# io-board-e-2.net
KiCad netlist of a schematic drawn in EAGLE
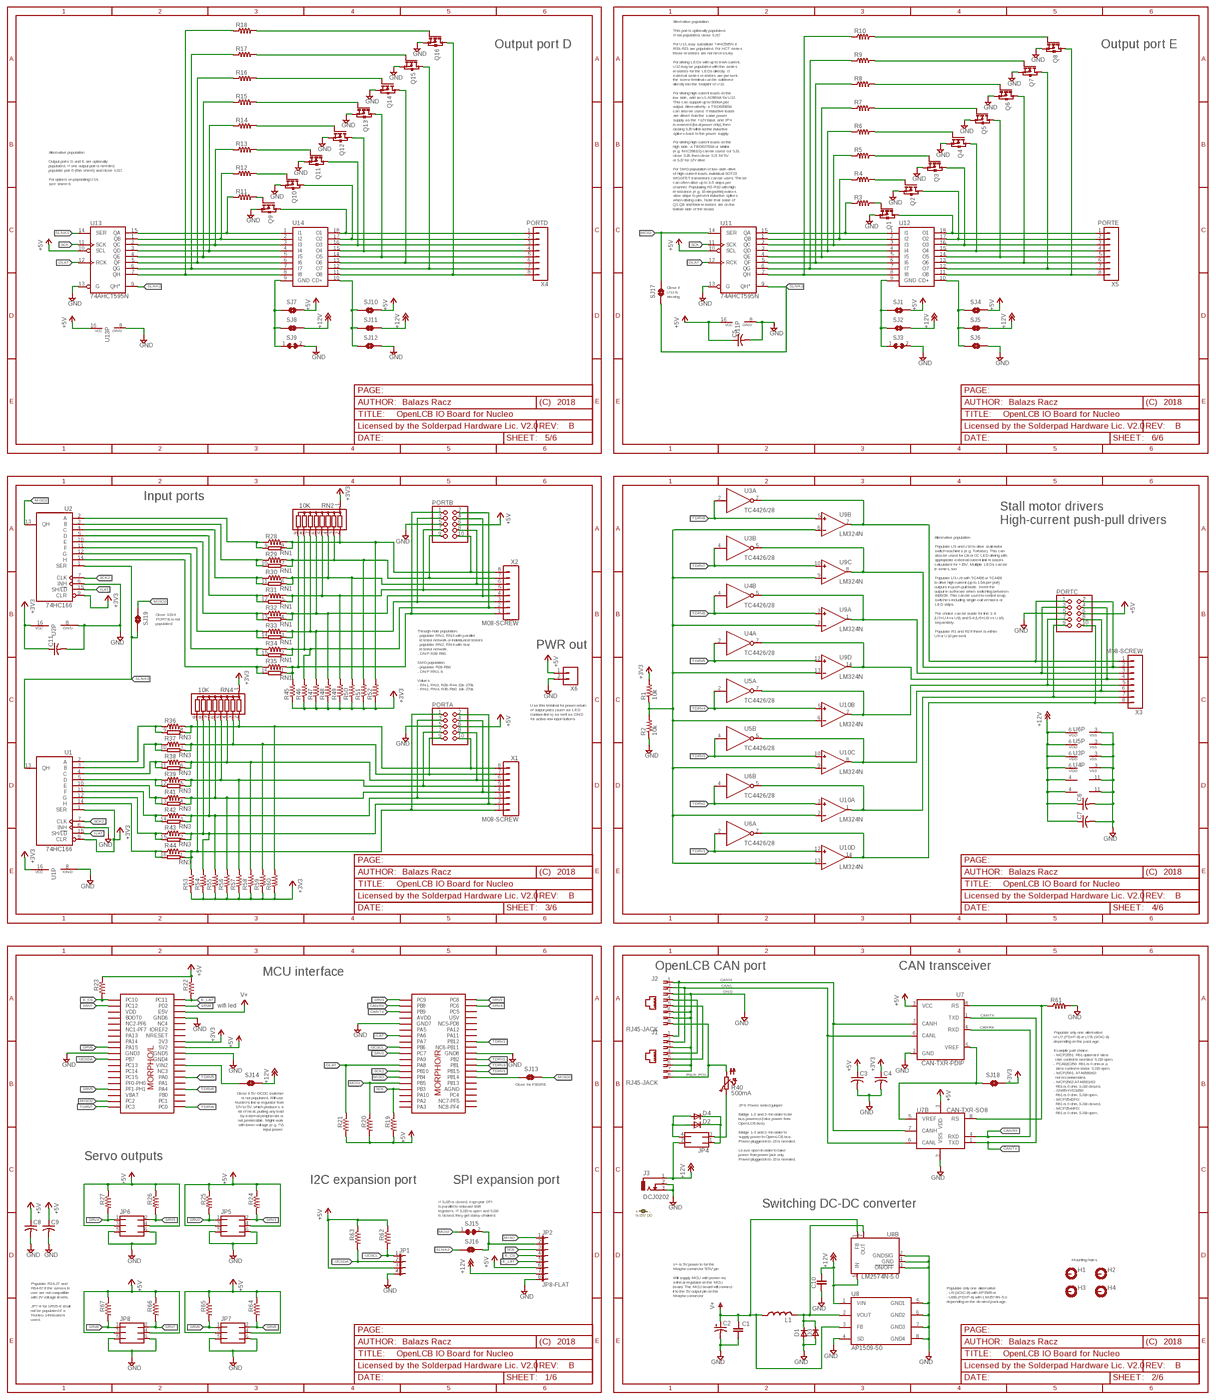
[diagram p0: schematic, sheet 1, overview]
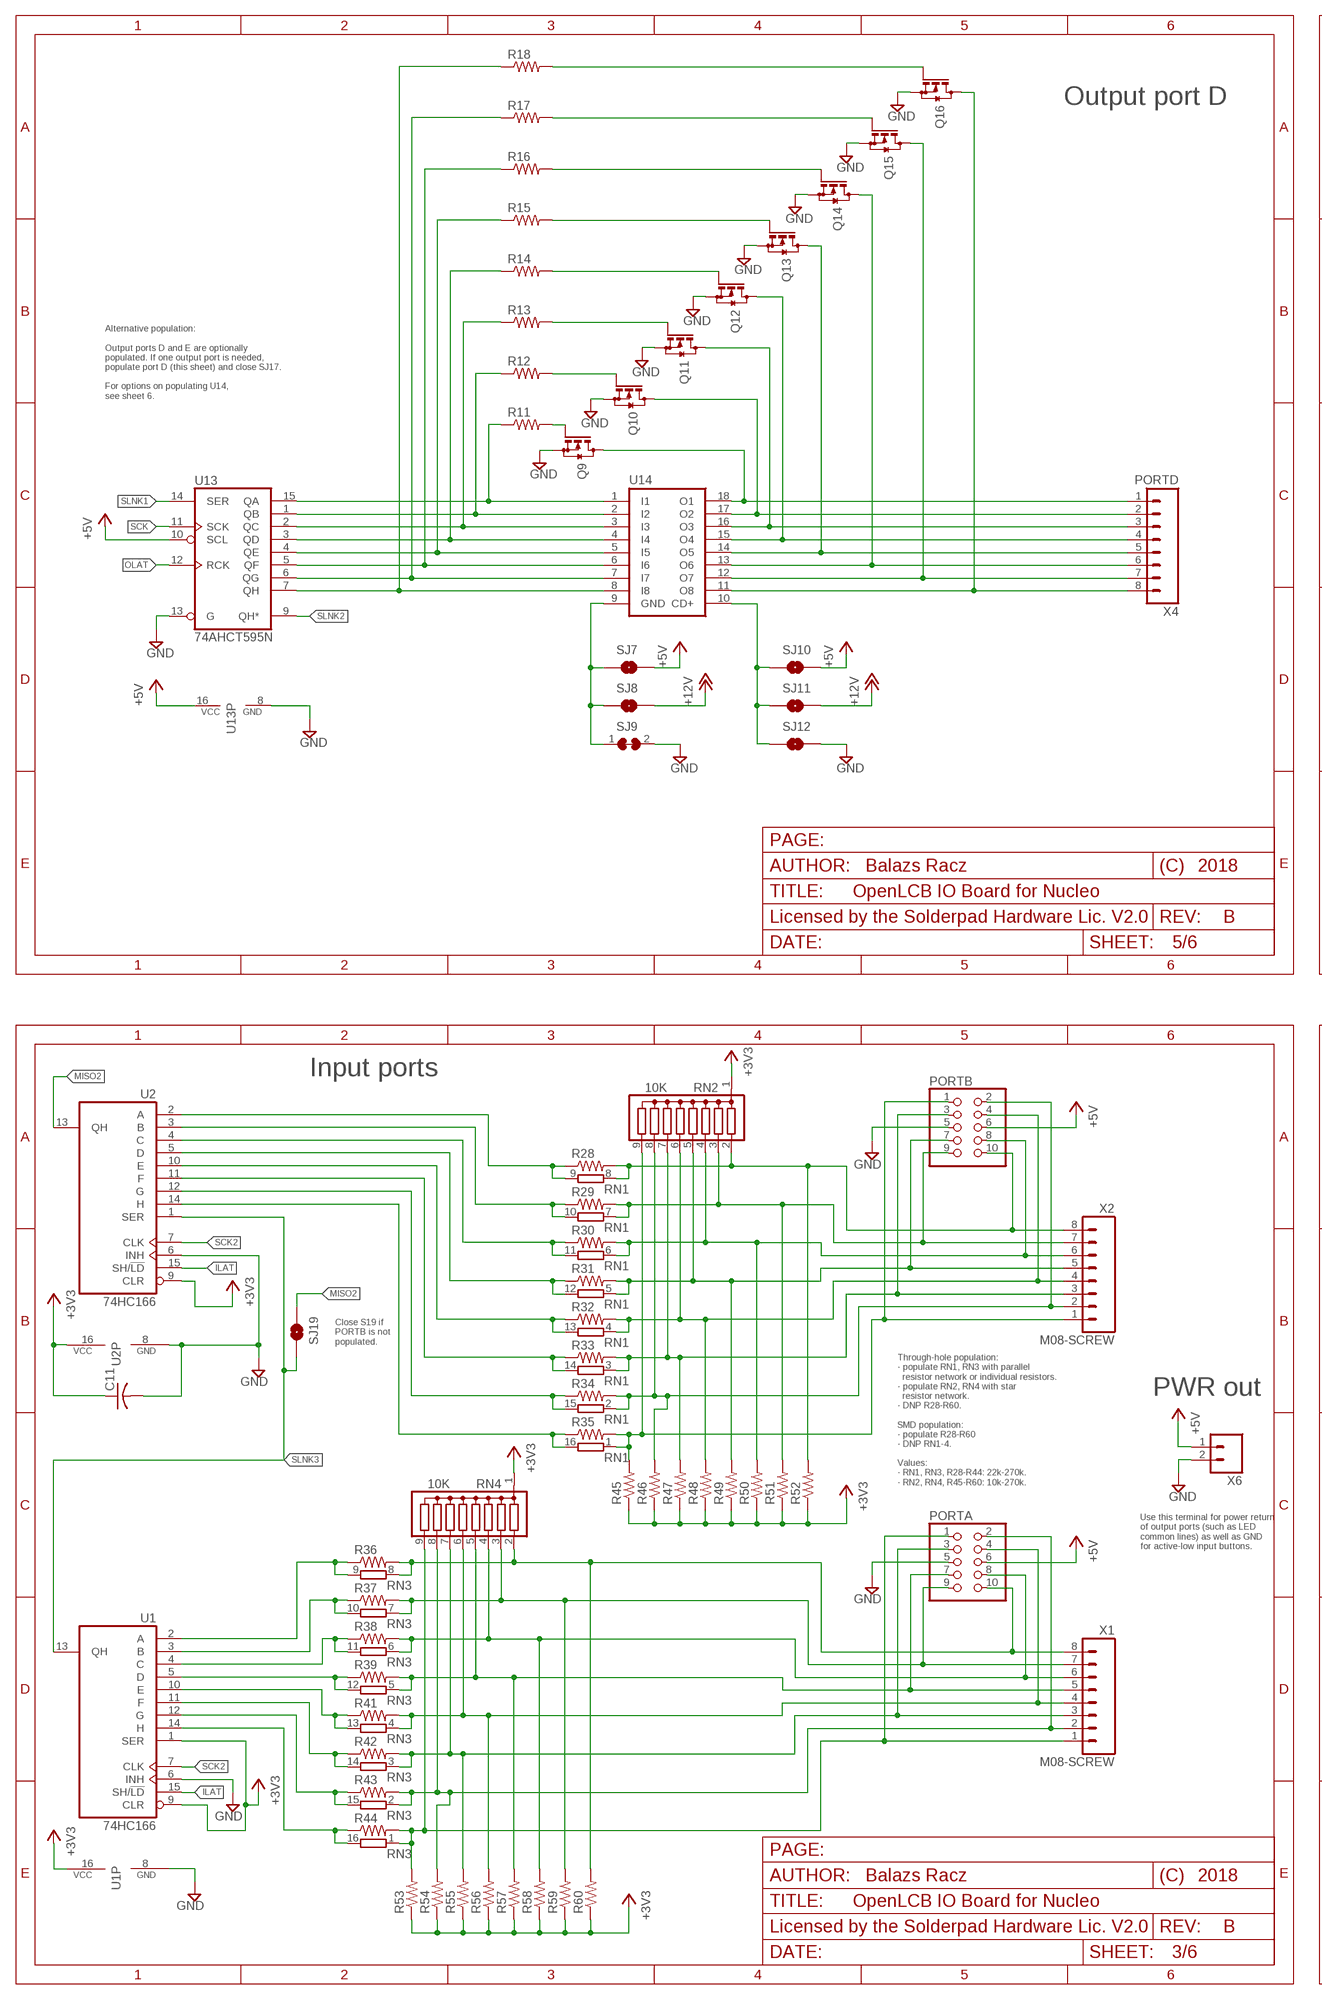
[diagram p1: schematic, sheet 1, part 1 of 4]
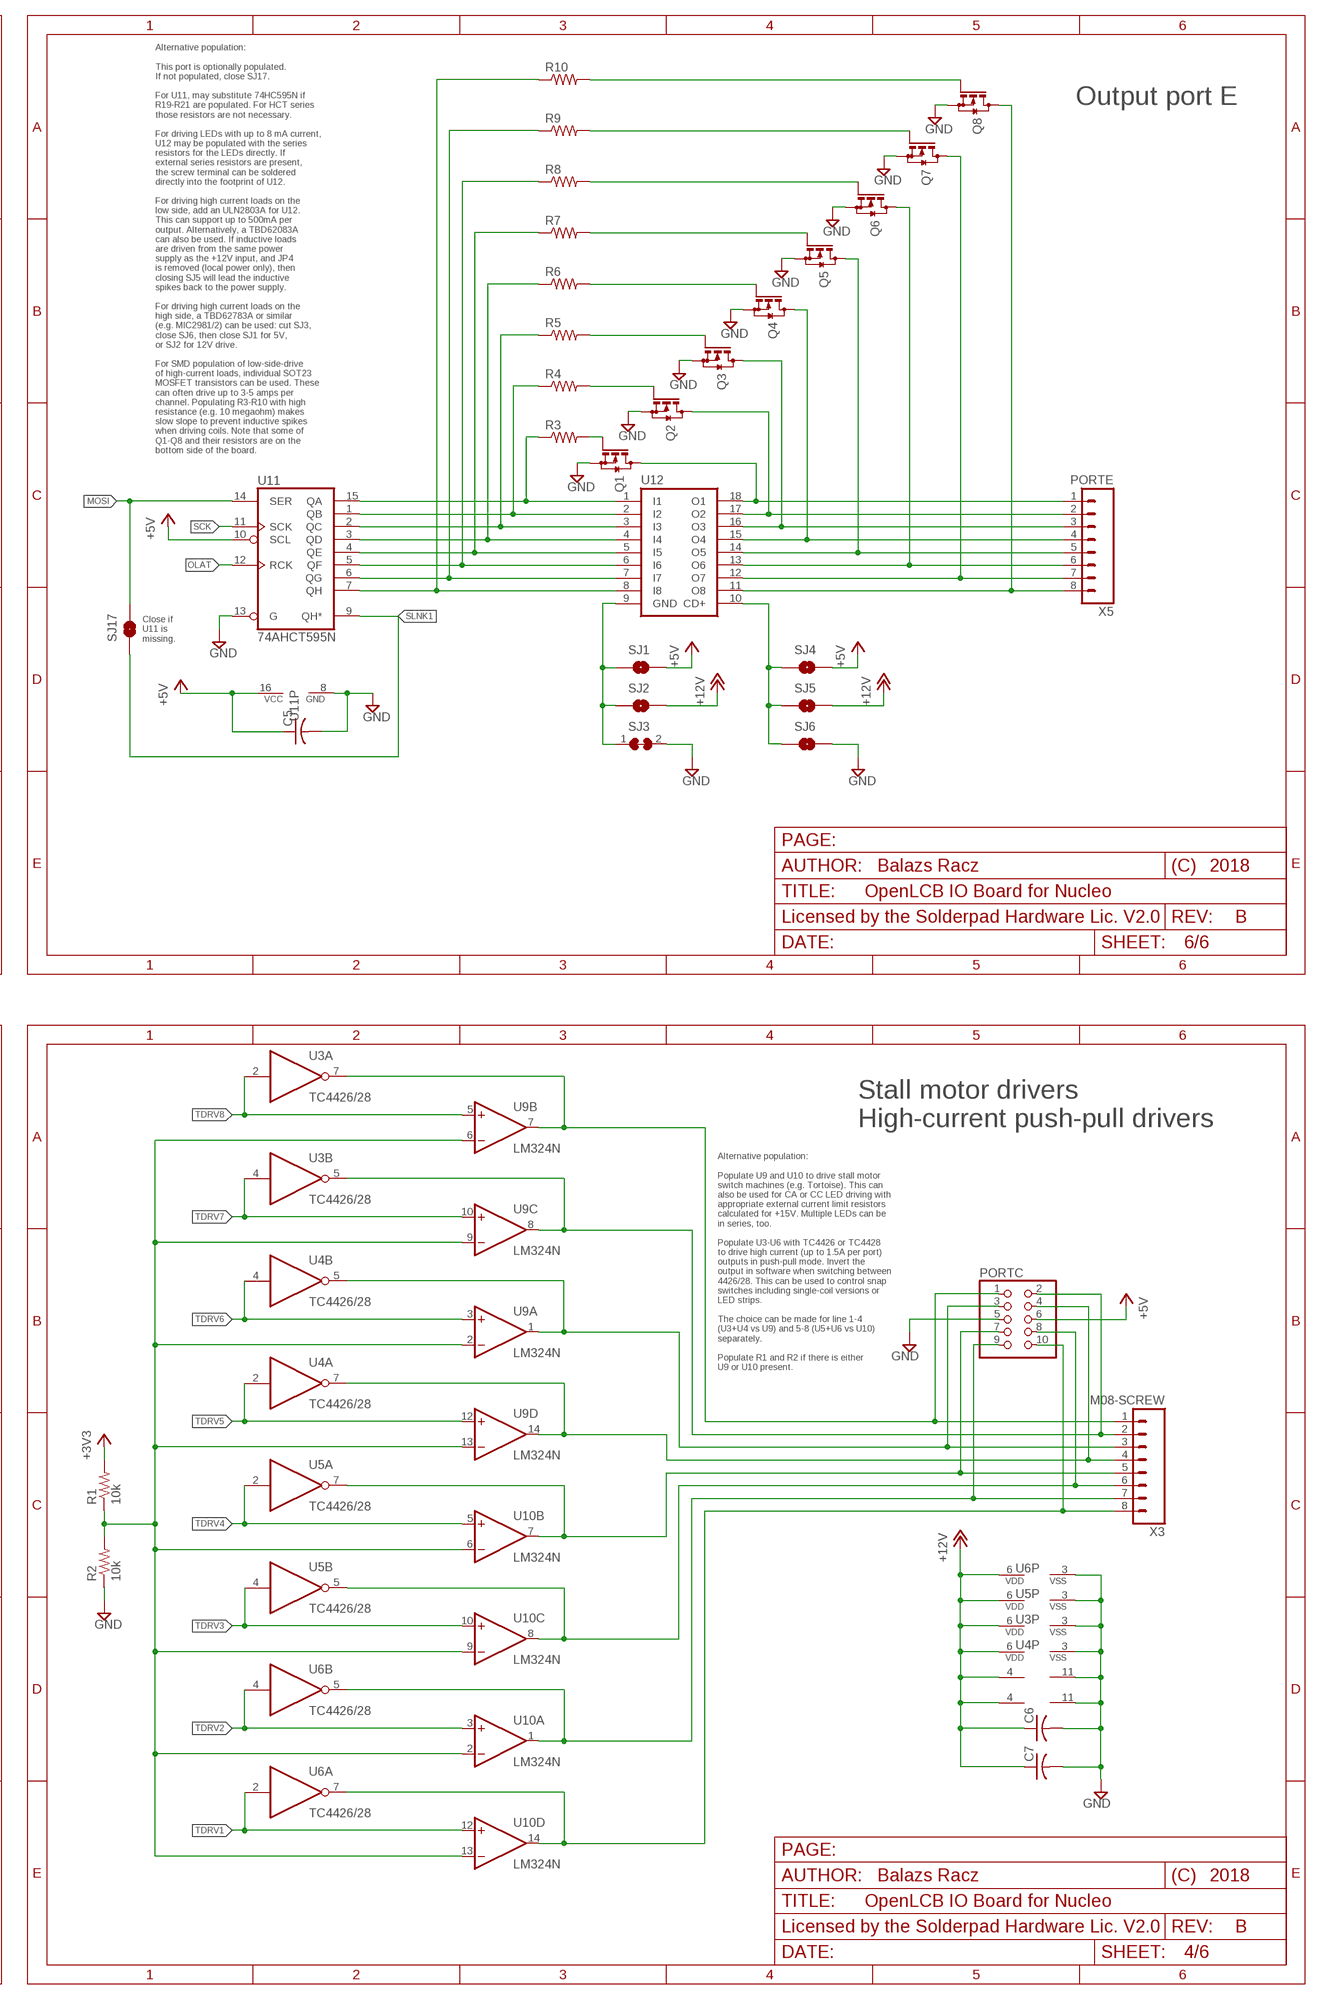
[diagram p2: schematic, sheet 1, part 2 of 4]
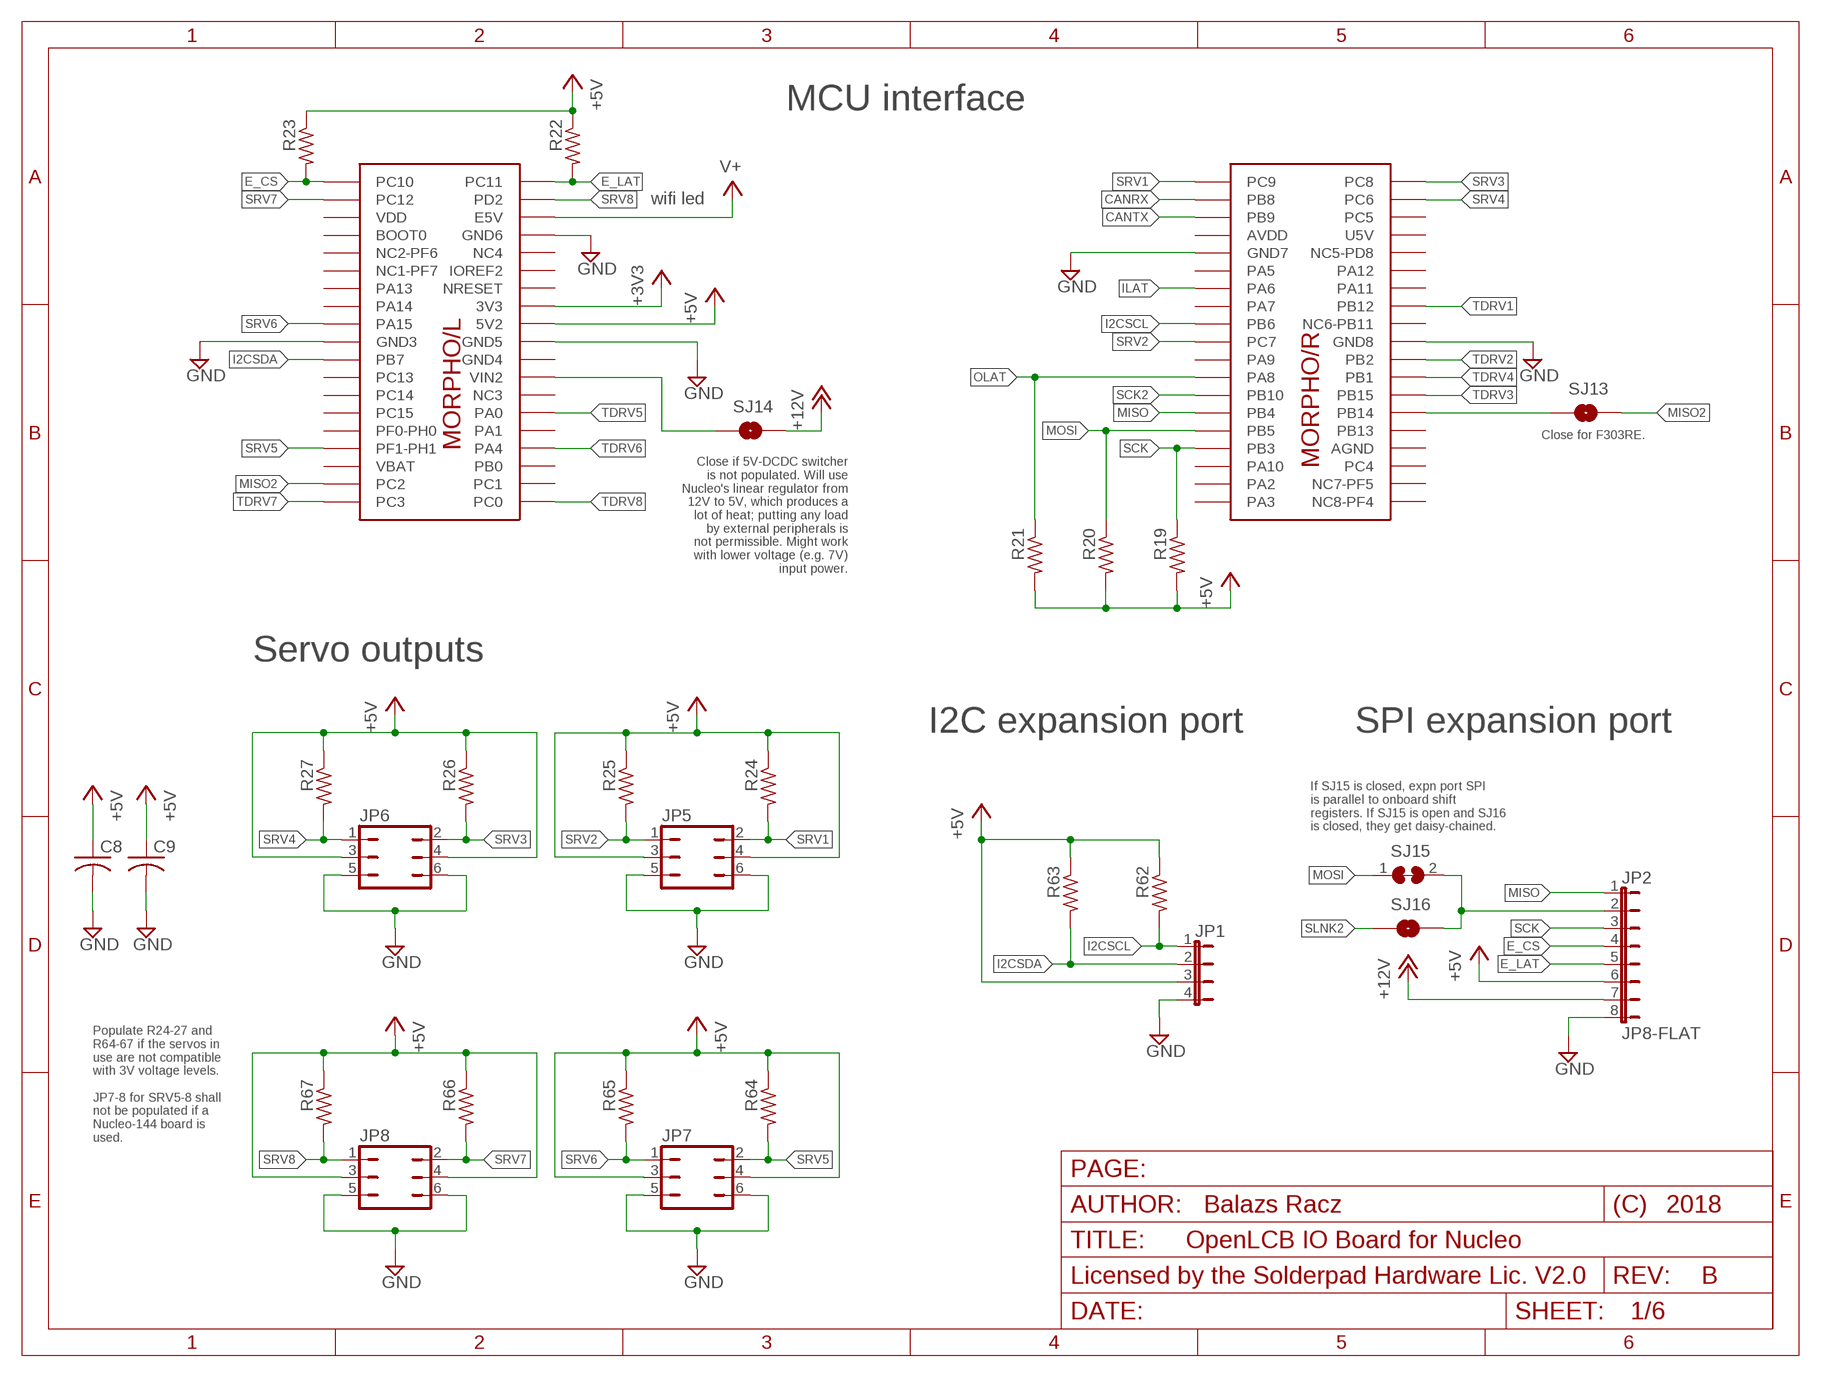
[diagram p3: schematic, sheet 1, part 3 of 4]
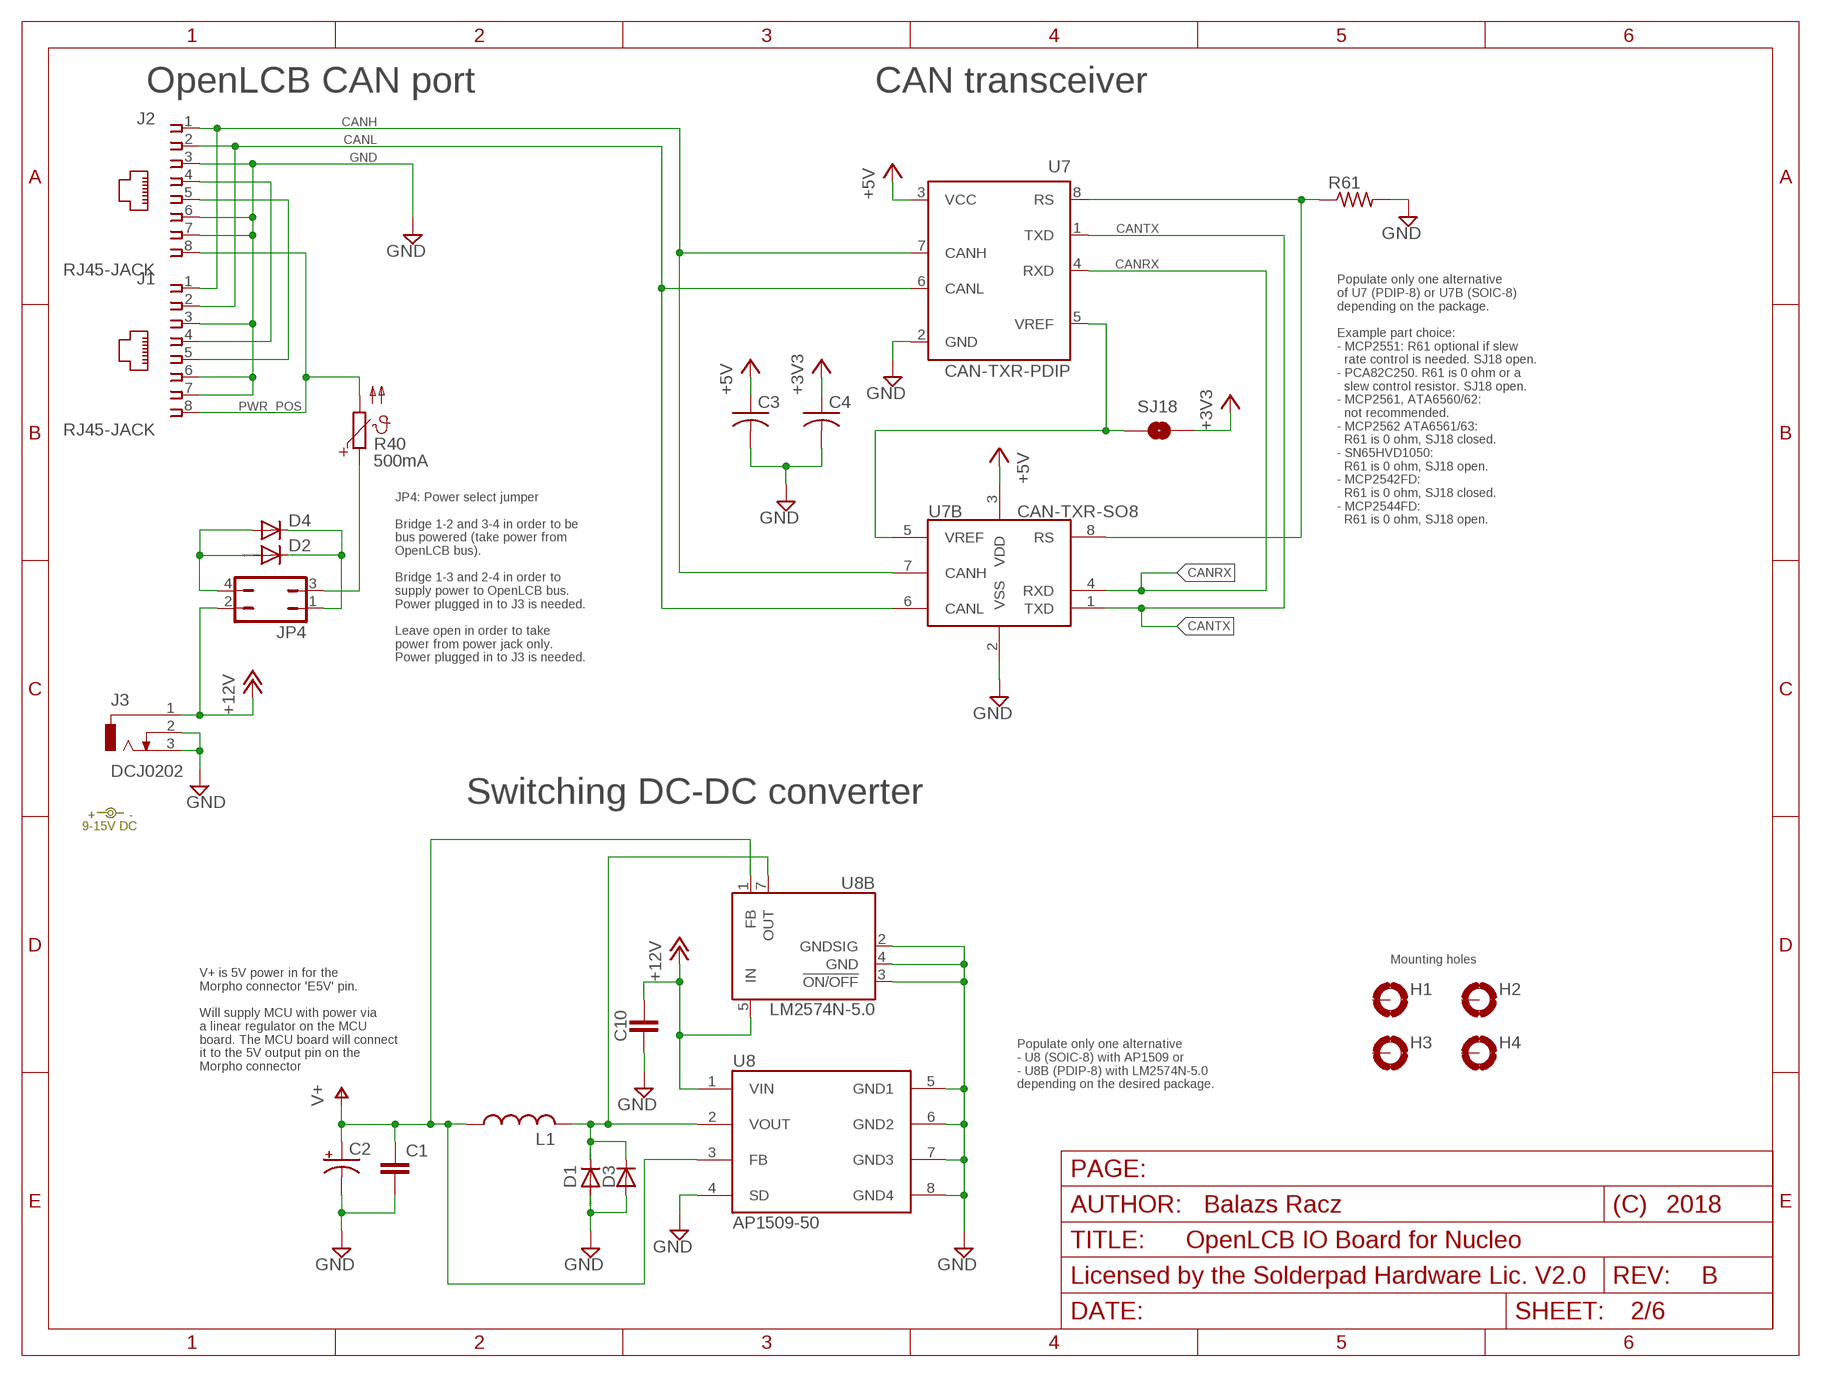
[diagram p4: schematic, sheet 1, part 4 of 4]

(export (version "E")
  (design (tool "Eeschema 10.0.6"))
  (components
    (comp (ref "+12V")
      (value "9-15V DC")
      (footprint "eagle-import:POWER_USAGE")
      (libsource (lib "eagle-import") (part "DOC-POWER_LABEL"))
    )
    (comp (ref "C1")
      (value "C-EUC1206")
      (footprint "eagle-import:C1206")
      (libsource (lib "eagle-import") (part "C-EUC1206"))
    )
    (comp (ref "C2")
      (value "CPOL-USE2.5-5")
      (footprint "eagle-import:E2,5-5")
      (libsource (lib "eagle-import") (part "CPOL-USE2.5-5"))
    )
    (comp (ref "C3")
      (value "C-USC0805")
      (footprint "eagle-import:C0805")
      (libsource (lib "eagle-import") (part "C-USC0805"))
    )
    (comp (ref "C4")
      (value "C-USC0805")
      (footprint "eagle-import:C0805")
      (libsource (lib "eagle-import") (part "C-USC0805"))
    )
    (comp (ref "C5")
      (value "C-USC0805")
      (footprint "eagle-import:C0805")
      (libsource (lib "eagle-import") (part "C-USC0805"))
    )
    (comp (ref "C6")
      (value "C-USC1206")
      (footprint "eagle-import:C1206")
      (libsource (lib "eagle-import") (part "C-USC1206"))
    )
    (comp (ref "C7")
      (value "C-USC1206")
      (footprint "eagle-import:C1206")
      (libsource (lib "eagle-import") (part "C-USC1206"))
    )
    (comp (ref "C8")
      (value "C-USC1206")
      (footprint "eagle-import:C1206")
      (libsource (lib "eagle-import") (part "C-USC1206"))
    )
    (comp (ref "C9")
      (value "C-USC1206")
      (footprint "eagle-import:C1206")
      (libsource (lib "eagle-import") (part "C-USC1206"))
    )
    (comp (ref "C10")
      (value "C-EUC1206")
      (footprint "eagle-import:C1206")
      (libsource (lib "eagle-import") (part "C-EUC1206"))
    )
    (comp (ref "C11")
      (value "C-USC0805")
      (footprint "eagle-import:C0805")
      (libsource (lib "eagle-import") (part "C-USC0805"))
    )
    (comp (ref "D1")
      (value "DIODE-DO41-7.6")
      (footprint "eagle-import:DO41-7.6")
      (libsource (lib "eagle-import") (part "DIODE-DO41-7.6"))
    )
    (comp (ref "D2")
      (value "DIODE-DO41-7.6")
      (footprint "eagle-import:DO41-7.6")
      (libsource (lib "eagle-import") (part "DIODE-DO41-7.6"))
    )
    (comp (ref "D3")
      (value "DIODEDO-214AA-NODOC")
      (footprint "eagle-import:DO214AA-NODOC")
      (libsource (lib "eagle-import") (part "DIODEDO-214AA-NODOC"))
    )
    (comp (ref "D4")
      (value "DIODEDO-214AA-NODOC")
      (footprint "eagle-import:DO214AA-NODOC")
      (libsource (lib "eagle-import") (part "DIODEDO-214AA-NODOC"))
    )
    (comp (ref "H1")
      (value "MOUNT-PAD-ROUND3.3")
      (footprint "eagle-import:3,3-PAD")
      (libsource (lib "eagle-import") (part "MOUNT-PAD-ROUND3.3"))
    )
    (comp (ref "H2")
      (value "MOUNT-PAD-ROUND3.3")
      (footprint "eagle-import:3,3-PAD")
      (libsource (lib "eagle-import") (part "MOUNT-PAD-ROUND3.3"))
    )
    (comp (ref "H3")
      (value "MOUNT-PAD-ROUND3.3")
      (footprint "eagle-import:3,3-PAD")
      (libsource (lib "eagle-import") (part "MOUNT-PAD-ROUND3.3"))
    )
    (comp (ref "H4")
      (value "MOUNT-PAD-ROUND3.3")
      (footprint "eagle-import:3,3-PAD")
      (libsource (lib "eagle-import") (part "MOUNT-PAD-ROUND3.3"))
    )
    (comp (ref "J1")
      (value "RJ45-JACK")
      (footprint "eagle-import:RJ45-PULSE-E5J88")
      (libsource (lib "eagle-import") (part "RJ45-JACKRJ45-PULSE-E5J00"))
    )
    (comp (ref "J2")
      (value "RJ45-JACK")
      (footprint "eagle-import:RJ45-PULSE-E5J88")
      (libsource (lib "eagle-import") (part "RJ45-JACKRJ45-PULSE-E5J00"))
    )
    (comp (ref "J3")
      (value "DCJ0202")
      (footprint "eagle-import:DCJ0202")
      (libsource (lib "eagle-import") (part "DCJ0202"))
    )
    (comp (ref "JP1")
      (value "JP4-FLAT")
      (footprint "eagle-import:JP4F")
      (libsource (lib "eagle-import") (part "JP4-FLAT"))
    )
    (comp (ref "JP2")
      (value "JP8-FLAT")
      (footprint "eagle-import:JP8F")
      (libsource (lib "eagle-import") (part "JP8-FLAT"))
    )
    (comp (ref "JP4")
      (value "JP2Q")
      (footprint "eagle-import:JP2Q")
      (libsource (lib "eagle-import") (part "JP2Q"))
    )
    (comp (ref "JP5")
      (value "JP3Q")
      (footprint "eagle-import:JP3Q")
      (libsource (lib "eagle-import") (part "JP3Q"))
    )
    (comp (ref "JP6")
      (value "JP3Q")
      (footprint "eagle-import:JP3Q")
      (libsource (lib "eagle-import") (part "JP3Q"))
    )
    (comp (ref "JP7")
      (value "JP3Q")
      (footprint "eagle-import:JP3Q")
      (libsource (lib "eagle-import") (part "JP3Q"))
    )
    (comp (ref "JP8")
      (value "JP3Q")
      (footprint "eagle-import:JP3Q")
      (libsource (lib "eagle-import") (part "JP3Q"))
    )
    (comp (ref "L1")
      (value "L-US")
      (footprint "eagle-import:L5-8,5")
      (libsource (lib "eagle-import") (part "L-US"))
    )
    (comp (ref "PORTA")
      (value "PINHD-2X5CN")
      (footprint "eagle-import:CON10M")
      (libsource (lib "eagle-import") (part "PINHD-2X5CN"))
    )
    (comp (ref "PORTB")
      (value "PINHD-2X5CN")
      (footprint "eagle-import:CON10M")
      (libsource (lib "eagle-import") (part "PINHD-2X5CN"))
    )
    (comp (ref "PORTC")
      (value "PINHD-2X5CN")
      (footprint "eagle-import:CON10M")
      (libsource (lib "eagle-import") (part "PINHD-2X5CN"))
    )
    (comp (ref "Q1")
      (value "BSS123")
      (footprint "eagle-import:SOT23")
      (libsource (lib "eagle-import") (part "BSS123"))
    )
    (comp (ref "Q2")
      (value "BSS123")
      (footprint "eagle-import:SOT23")
      (libsource (lib "eagle-import") (part "BSS123"))
    )
    (comp (ref "Q3")
      (value "BSS123")
      (footprint "eagle-import:SOT23")
      (libsource (lib "eagle-import") (part "BSS123"))
    )
    (comp (ref "Q4")
      (value "BSS123")
      (footprint "eagle-import:SOT23")
      (libsource (lib "eagle-import") (part "BSS123"))
    )
    (comp (ref "Q5")
      (value "BSS123")
      (footprint "eagle-import:SOT23")
      (libsource (lib "eagle-import") (part "BSS123"))
    )
    (comp (ref "Q6")
      (value "BSS123")
      (footprint "eagle-import:SOT23")
      (libsource (lib "eagle-import") (part "BSS123"))
    )
    (comp (ref "Q7")
      (value "BSS123")
      (footprint "eagle-import:SOT23")
      (libsource (lib "eagle-import") (part "BSS123"))
    )
    (comp (ref "Q8")
      (value "BSS123")
      (footprint "eagle-import:SOT23")
      (libsource (lib "eagle-import") (part "BSS123"))
    )
    (comp (ref "Q9")
      (value "BSS123")
      (footprint "eagle-import:SOT23")
      (libsource (lib "eagle-import") (part "BSS123"))
    )
    (comp (ref "Q10")
      (value "BSS123")
      (footprint "eagle-import:SOT23")
      (libsource (lib "eagle-import") (part "BSS123"))
    )
    (comp (ref "Q11")
      (value "BSS123")
      (footprint "eagle-import:SOT23")
      (libsource (lib "eagle-import") (part "BSS123"))
    )
    (comp (ref "Q12")
      (value "BSS123")
      (footprint "eagle-import:SOT23")
      (libsource (lib "eagle-import") (part "BSS123"))
    )
    (comp (ref "Q13")
      (value "BSS123")
      (footprint "eagle-import:SOT23")
      (libsource (lib "eagle-import") (part "BSS123"))
    )
    (comp (ref "Q14")
      (value "BSS123")
      (footprint "eagle-import:SOT23")
      (libsource (lib "eagle-import") (part "BSS123"))
    )
    (comp (ref "Q15")
      (value "BSS123")
      (footprint "eagle-import:SOT23")
      (libsource (lib "eagle-import") (part "BSS123"))
    )
    (comp (ref "Q16")
      (value "BSS123")
      (footprint "eagle-import:SOT23")
      (libsource (lib "eagle-import") (part "BSS123"))
    )
    (comp (ref "R1")
      (value "10k")
      (footprint "eagle-import:R0805")
      (libsource (lib "eagle-import") (part "R-US_R0805"))
    )
    (comp (ref "R2")
      (value "10k")
      (footprint "eagle-import:R0805")
      (libsource (lib "eagle-import") (part "R-US_R0805"))
    )
    (comp (ref "R3")
      (value "R-US_R0603")
      (footprint "eagle-import:R0603")
      (libsource (lib "eagle-import") (part "R-US_R0603"))
    )
    (comp (ref "R4")
      (value "R-US_R0603")
      (footprint "eagle-import:R0603")
      (libsource (lib "eagle-import") (part "R-US_R0603"))
    )
    (comp (ref "R5")
      (value "R-US_R0603")
      (footprint "eagle-import:R0603")
      (libsource (lib "eagle-import") (part "R-US_R0603"))
    )
    (comp (ref "R6")
      (value "R-US_R0603")
      (footprint "eagle-import:R0603")
      (libsource (lib "eagle-import") (part "R-US_R0603"))
    )
    (comp (ref "R7")
      (value "R-US_R0603")
      (footprint "eagle-import:R0603")
      (libsource (lib "eagle-import") (part "R-US_R0603"))
    )
    (comp (ref "R8")
      (value "R-US_R0603")
      (footprint "eagle-import:R0603")
      (libsource (lib "eagle-import") (part "R-US_R0603"))
    )
    (comp (ref "R9")
      (value "R-US_R0603")
      (footprint "eagle-import:R0603")
      (libsource (lib "eagle-import") (part "R-US_R0603"))
    )
    (comp (ref "R10")
      (value "R-US_R0603")
      (footprint "eagle-import:R0603")
      (libsource (lib "eagle-import") (part "R-US_R0603"))
    )
    (comp (ref "R11")
      (value "R-US_R0603")
      (footprint "eagle-import:R0603")
      (libsource (lib "eagle-import") (part "R-US_R0603"))
    )
    (comp (ref "R12")
      (value "R-US_R0603")
      (footprint "eagle-import:R0603")
      (libsource (lib "eagle-import") (part "R-US_R0603"))
    )
    (comp (ref "R13")
      (value "R-US_R0603")
      (footprint "eagle-import:R0603")
      (libsource (lib "eagle-import") (part "R-US_R0603"))
    )
    (comp (ref "R14")
      (value "R-US_R0603")
      (footprint "eagle-import:R0603")
      (libsource (lib "eagle-import") (part "R-US_R0603"))
    )
    (comp (ref "R15")
      (value "R-US_R0603")
      (footprint "eagle-import:R0603")
      (libsource (lib "eagle-import") (part "R-US_R0603"))
    )
    (comp (ref "R16")
      (value "R-US_R0603")
      (footprint "eagle-import:R0603")
      (libsource (lib "eagle-import") (part "R-US_R0603"))
    )
    (comp (ref "R17")
      (value "R-US_R0603")
      (footprint "eagle-import:R0603")
      (libsource (lib "eagle-import") (part "R-US_R0603"))
    )
    (comp (ref "R18")
      (value "R-US_R0603")
      (footprint "eagle-import:R0603")
      (libsource (lib "eagle-import") (part "R-US_R0603"))
    )
    (comp (ref "R19")
      (value "R-US_R0805")
      (footprint "eagle-import:R0805")
      (libsource (lib "eagle-import") (part "rcl_334_R-US_R0805"))
    )
    (comp (ref "R20")
      (value "R-US_R0805")
      (footprint "eagle-import:R0805")
      (libsource (lib "eagle-import") (part "rcl_334_R-US_R0805"))
    )
    (comp (ref "R21")
      (value "R-US_R0805")
      (footprint "eagle-import:R0805")
      (libsource (lib "eagle-import") (part "rcl_334_R-US_R0805"))
    )
    (comp (ref "R22")
      (value "R-US_R0805")
      (footprint "eagle-import:R0805")
      (libsource (lib "eagle-import") (part "rcl_334_R-US_R0805"))
    )
    (comp (ref "R23")
      (value "R-US_R0805")
      (footprint "eagle-import:R0805")
      (libsource (lib "eagle-import") (part "rcl_334_R-US_R0805"))
    )
    (comp (ref "R24")
      (value "R-US_R0805")
      (footprint "eagle-import:R0805")
      (libsource (lib "eagle-import") (part "rcl_334_R-US_R0805"))
    )
    (comp (ref "R25")
      (value "R-US_R0805")
      (footprint "eagle-import:R0805")
      (libsource (lib "eagle-import") (part "rcl_334_R-US_R0805"))
    )
    (comp (ref "R26")
      (value "R-US_R0805")
      (footprint "eagle-import:R0805")
      (libsource (lib "eagle-import") (part "rcl_334_R-US_R0805"))
    )
    (comp (ref "R27")
      (value "R-US_R0805")
      (footprint "eagle-import:R0805")
      (libsource (lib "eagle-import") (part "rcl_334_R-US_R0805"))
    )
    (comp (ref "R28")
      (value "R-US_R0603")
      (footprint "eagle-import:R0603")
      (libsource (lib "eagle-import") (part "rcl_334_R-US_R0603"))
    )
    (comp (ref "R29")
      (value "R-US_R0603")
      (footprint "eagle-import:R0603")
      (libsource (lib "eagle-import") (part "rcl_334_R-US_R0603"))
    )
    (comp (ref "R30")
      (value "R-US_R0603")
      (footprint "eagle-import:R0603")
      (libsource (lib "eagle-import") (part "rcl_334_R-US_R0603"))
    )
    (comp (ref "R31")
      (value "R-US_R0603")
      (footprint "eagle-import:R0603")
      (libsource (lib "eagle-import") (part "rcl_334_R-US_R0603"))
    )
    (comp (ref "R32")
      (value "R-US_R0603")
      (footprint "eagle-import:R0603")
      (libsource (lib "eagle-import") (part "rcl_334_R-US_R0603"))
    )
    (comp (ref "R33")
      (value "R-US_R0603")
      (footprint "eagle-import:R0603")
      (libsource (lib "eagle-import") (part "rcl_334_R-US_R0603"))
    )
    (comp (ref "R34")
      (value "R-US_R0603")
      (footprint "eagle-import:R0603")
      (libsource (lib "eagle-import") (part "rcl_334_R-US_R0603"))
    )
    (comp (ref "R35")
      (value "R-US_R0603")
      (footprint "eagle-import:R0603")
      (libsource (lib "eagle-import") (part "rcl_334_R-US_R0603"))
    )
    (comp (ref "R36")
      (value "R-US_R0603")
      (footprint "eagle-import:R0603")
      (libsource (lib "eagle-import") (part "rcl_334_R-US_R0603"))
    )
    (comp (ref "R37")
      (value "R-US_R0603")
      (footprint "eagle-import:R0603")
      (libsource (lib "eagle-import") (part "rcl_334_R-US_R0603"))
    )
    (comp (ref "R38")
      (value "R-US_R0603")
      (footprint "eagle-import:R0603")
      (libsource (lib "eagle-import") (part "rcl_334_R-US_R0603"))
    )
    (comp (ref "R39")
      (value "R-US_R0603")
      (footprint "eagle-import:R0603")
      (libsource (lib "eagle-import") (part "rcl_334_R-US_R0603"))
    )
    (comp (ref "R40")
      (value "500mA")
      (footprint "eagle-import:PTC1812")
      (libsource (lib "eagle-import") (part "PTC_1812"))
    )
    (comp (ref "R41")
      (value "R-US_R0603")
      (footprint "eagle-import:R0603")
      (libsource (lib "eagle-import") (part "rcl_334_R-US_R0603"))
    )
    (comp (ref "R42")
      (value "R-US_R0603")
      (footprint "eagle-import:R0603")
      (libsource (lib "eagle-import") (part "rcl_334_R-US_R0603"))
    )
    (comp (ref "R43")
      (value "R-US_R0603")
      (footprint "eagle-import:R0603")
      (libsource (lib "eagle-import") (part "rcl_334_R-US_R0603"))
    )
    (comp (ref "R44")
      (value "R-US_R0603")
      (footprint "eagle-import:R0603")
      (libsource (lib "eagle-import") (part "rcl_334_R-US_R0603"))
    )
    (comp (ref "R45")
      (value "R-US")
      (footprint "eagle-import:R0603")
      (libsource (lib "eagle-import") (part "R-US"))
    )
    (comp (ref "R46")
      (value "R-US")
      (footprint "eagle-import:R0603")
      (libsource (lib "eagle-import") (part "R-US"))
    )
    (comp (ref "R47")
      (value "R-US")
      (footprint "eagle-import:R0603")
      (libsource (lib "eagle-import") (part "R-US"))
    )
    (comp (ref "R48")
      (value "R-US")
      (footprint "eagle-import:R0603")
      (libsource (lib "eagle-import") (part "R-US"))
    )
    (comp (ref "R49")
      (value "R-US")
      (footprint "eagle-import:R0603")
      (libsource (lib "eagle-import") (part "R-US"))
    )
    (comp (ref "R50")
      (value "R-US")
      (footprint "eagle-import:R0603")
      (libsource (lib "eagle-import") (part "R-US"))
    )
    (comp (ref "R51")
      (value "R-US")
      (footprint "eagle-import:R0603")
      (libsource (lib "eagle-import") (part "R-US"))
    )
    (comp (ref "R52")
      (value "R-US")
      (footprint "eagle-import:R0603")
      (libsource (lib "eagle-import") (part "R-US"))
    )
    (comp (ref "R53")
      (value "R-US")
      (footprint "eagle-import:R0603")
      (libsource (lib "eagle-import") (part "R-US"))
    )
    (comp (ref "R54")
      (value "R-US")
      (footprint "eagle-import:R0603")
      (libsource (lib "eagle-import") (part "R-US"))
    )
    (comp (ref "R55")
      (value "R-US")
      (footprint "eagle-import:R0603")
      (libsource (lib "eagle-import") (part "R-US"))
    )
    (comp (ref "R56")
      (value "R-US")
      (footprint "eagle-import:R0603")
      (libsource (lib "eagle-import") (part "R-US"))
    )
    (comp (ref "R57")
      (value "R-US")
      (footprint "eagle-import:R0603")
      (libsource (lib "eagle-import") (part "R-US"))
    )
    (comp (ref "R58")
      (value "R-US")
      (footprint "eagle-import:R0603")
      (libsource (lib "eagle-import") (part "R-US"))
    )
    (comp (ref "R59")
      (value "R-US")
      (footprint "eagle-import:R0603")
      (libsource (lib "eagle-import") (part "R-US"))
    )
    (comp (ref "R60")
      (value "R-US")
      (footprint "eagle-import:R0603")
      (libsource (lib "eagle-import") (part "R-US"))
    )
    (comp (ref "R61")
      (value "R-US_R0805")
      (footprint "eagle-import:R0805")
      (libsource (lib "eagle-import") (part "rcl_334_R-US_R0805"))
    )
    (comp (ref "R62")
      (value "R-US_R0805")
      (footprint "eagle-import:R0805")
      (libsource (lib "eagle-import") (part "rcl_334_R-US_R0805"))
    )
    (comp (ref "R63")
      (value "R-US_R0805")
      (footprint "eagle-import:R0805")
      (libsource (lib "eagle-import") (part "rcl_334_R-US_R0805"))
    )
    (comp (ref "R64")
      (value "R-US_R0805")
      (footprint "eagle-import:R0805")
      (libsource (lib "eagle-import") (part "rcl_334_R-US_R0805"))
    )
    (comp (ref "R65")
      (value "R-US_R0805")
      (footprint "eagle-import:R0805")
      (libsource (lib "eagle-import") (part "rcl_334_R-US_R0805"))
    )
    (comp (ref "R66")
      (value "R-US_R0805")
      (footprint "eagle-import:R0805")
      (libsource (lib "eagle-import") (part "rcl_334_R-US_R0805"))
    )
    (comp (ref "R67")
      (value "R-US_R0805")
      (footprint "eagle-import:R0805")
      (libsource (lib "eagle-import") (part "rcl_334_R-US_R0805"))
    )
    (comp (ref "RN1")
      (value "8R-P")
      (footprint "eagle-import:DIL16")
      (libsource (lib "eagle-import") (part "8R-P"))
    )
    (comp (ref "RN2")
      (value "10K")
      (footprint "eagle-import:SIL9")
      (libsource (lib "eagle-import") (part "G08R"))
    )
    (comp (ref "RN3")
      (value "8R-P")
      (footprint "eagle-import:DIL16")
      (libsource (lib "eagle-import") (part "8R-P"))
    )
    (comp (ref "RN4")
      (value "10K")
      (footprint "eagle-import:SIL9")
      (libsource (lib "eagle-import") (part "G08R"))
    )
    (comp (ref "SJ1")
      (value "SJRND2")
      (footprint "eagle-import:SJ_RND2")
      (libsource (lib "eagle-import") (part "SJRND2"))
    )
    (comp (ref "SJ2")
      (value "SJRND2")
      (footprint "eagle-import:SJ_RND2")
      (libsource (lib "eagle-import") (part "SJRND2"))
    )
    (comp (ref "SJ3")
      (value "SJ-C")
      (footprint "eagle-import:SJW-C")
      (libsource (lib "eagle-import") (part "SJ-C"))
    )
    (comp (ref "SJ4")
      (value "SJRND2")
      (footprint "eagle-import:SJ_RND2")
      (libsource (lib "eagle-import") (part "SJRND2"))
    )
    (comp (ref "SJ5")
      (value "SJRND2")
      (footprint "eagle-import:SJ_RND2")
      (libsource (lib "eagle-import") (part "SJRND2"))
    )
    (comp (ref "SJ6")
      (value "SJRND2")
      (footprint "eagle-import:SJ_RND2")
      (libsource (lib "eagle-import") (part "SJRND2"))
    )
    (comp (ref "SJ7")
      (value "SJRND2")
      (footprint "eagle-import:SJ_RND2")
      (libsource (lib "eagle-import") (part "SJRND2"))
    )
    (comp (ref "SJ8")
      (value "SJRND2")
      (footprint "eagle-import:SJ_RND2")
      (libsource (lib "eagle-import") (part "SJRND2"))
    )
    (comp (ref "SJ9")
      (value "SJ-C")
      (footprint "eagle-import:SJW-C")
      (libsource (lib "eagle-import") (part "SJ-C"))
    )
    (comp (ref "SJ10")
      (value "SJRND2")
      (footprint "eagle-import:SJ_RND2")
      (libsource (lib "eagle-import") (part "SJRND2"))
    )
    (comp (ref "SJ11")
      (value "SJRND2")
      (footprint "eagle-import:SJ_RND2")
      (libsource (lib "eagle-import") (part "SJRND2"))
    )
    (comp (ref "SJ12")
      (value "SJRND2")
      (footprint "eagle-import:SJ_RND2")
      (libsource (lib "eagle-import") (part "SJRND2"))
    )
    (comp (ref "SJ13")
      (value "SJRND2")
      (footprint "eagle-import:SJ_RND2")
      (libsource (lib "eagle-import") (part "SJRND2"))
    )
    (comp (ref "SJ14")
      (value "SJRND2")
      (footprint "eagle-import:SJ_RND2")
      (libsource (lib "eagle-import") (part "SJRND2"))
    )
    (comp (ref "SJ15")
      (value "SJ-C")
      (footprint "eagle-import:SJW-C")
      (libsource (lib "eagle-import") (part "SJ-C"))
    )
    (comp (ref "SJ16")
      (value "SJRND2")
      (footprint "eagle-import:SJ_RND2")
      (libsource (lib "eagle-import") (part "SJRND2"))
    )
    (comp (ref "SJ17")
      (value "SJRND2")
      (footprint "eagle-import:SJ_RND2")
      (libsource (lib "eagle-import") (part "SJRND2"))
    )
    (comp (ref "SJ18")
      (value "SJRND2")
      (footprint "eagle-import:SJ_RND2")
      (libsource (lib "eagle-import") (part "SJRND2"))
    )
    (comp (ref "SJ19")
      (value "SJRND2")
      (footprint "eagle-import:SJ_RND2")
      (libsource (lib "eagle-import") (part "SJRND2"))
    )
    (comp (ref "U$1")
      (value "NUCLEO_64_GENERIC")
      (footprint "eagle-import:NUCLEO_BRD_BASE64")
      (libsource (lib "eagle-import") (part "NUCLEO_64_GENERIC"))
    )
    (comp (ref "U1")
      (value "74HC166")
      (footprint "eagle-import:DIL16")
      (libsource (lib "eagle-import") (part "74166N"))
    )
    (comp (ref "U2")
      (value "74HC166")
      (footprint "eagle-import:DIL16")
      (libsource (lib "eagle-import") (part "74166N"))
    )
    (comp (ref "U3")
      (value "TC4426/28")
      (footprint "eagle-import:DIL08-LONG")
      (libsource (lib "eagle-import") (part "TC4426APDIP"))
    )
    (comp (ref "U4")
      (value "TC4426/28")
      (footprint "eagle-import:DIL08-LONG")
      (libsource (lib "eagle-import") (part "TC4426APDIP"))
    )
    (comp (ref "U5")
      (value "TC4426/28")
      (footprint "eagle-import:DIL08-LONG")
      (libsource (lib "eagle-import") (part "TC4426APDIP"))
    )
    (comp (ref "U6")
      (value "TC4426/28")
      (footprint "eagle-import:DIL08-LONG")
      (libsource (lib "eagle-import") (part "TC4426APDIP"))
    )
    (comp (ref "U7")
      (value "CAN-TXR-PDIP")
      (footprint "eagle-import:DIL08")
      (libsource (lib "eagle-import") (part "PCA82C250"))
    )
    (comp (ref "U7B")
      (value "CAN-TXR-SO8")
      (footprint "eagle-import:SO-08")
      (libsource (lib "eagle-import") (part "MCP2551-SN"))
    )
    (comp (ref "U8")
      (value "AP1509-50")
      (footprint "eagle-import:SO-08")
      (libsource (lib "eagle-import") (part "AP1509"))
    )
    (comp (ref "U8B")
      (value "LM2574N-5.0")
      (footprint "eagle-import:DIL08")
      (libsource (lib "eagle-import") (part "LM2574?-N5.0"))
    )
    (comp (ref "U9")
      (value "LM324N")
      (footprint "eagle-import:DIL14")
      (libsource (lib "eagle-import") (part "LM324N"))
    )
    (comp (ref "U10")
      (value "LM324N")
      (footprint "eagle-import:DIL14")
      (libsource (lib "eagle-import") (part "LM324N"))
    )
    (comp (ref "U11")
      (value "74AHCT595N")
      (footprint "eagle-import:DIL16")
      (libsource (lib "eagle-import") (part "74595NHCT"))
    )
    (comp (ref "U12")
      (value "ULN2803A")
      (footprint "eagle-import:DIL18-THIN")
      (libsource (lib "eagle-import") (part "ULN2803A"))
    )
    (comp (ref "U13")
      (value "74AHCT595N")
      (footprint "eagle-import:DIL16")
      (libsource (lib "eagle-import") (part "74595NHCT"))
    )
    (comp (ref "U14")
      (value "ULN2803A")
      (footprint "eagle-import:DIL18-THIN")
      (libsource (lib "eagle-import") (part "ULN2803A"))
    )
    (comp (ref "X1")
      (value "M08-SCREW")
      (footprint "eagle-import:1X08_TERMINAL")
      (libsource (lib "eagle-import") (part "M08-SCREW"))
    )
    (comp (ref "X2")
      (value "M08-SCREW")
      (footprint "eagle-import:1X08_TERMINAL")
      (libsource (lib "eagle-import") (part "M08-SCREW"))
    )
    (comp (ref "X3")
      (value "M08-SCREW")
      (footprint "eagle-import:1X08_TERMINAL")
      (libsource (lib "eagle-import") (part "M08-SCREW"))
    )
    (comp (ref "X4")
      (value "PORTD")
      (footprint "eagle-import:1X08_TERMINAL")
      (libsource (lib "eagle-import") (part "M08-SCREW"))
    )
    (comp (ref "X5")
      (value "PORTE")
      (footprint "eagle-import:1X08_TERMINAL")
      (libsource (lib "eagle-import") (part "M08-SCREW"))
    )
    (comp (ref "X6")
      (value "CONNECTOR-M023.5MM-LOCK")
      (footprint "eagle-import:SCREWTERMINAL-3.5MM-2_LOCK")
      (libsource (lib "eagle-import") (part "CONNECTOR-M023.5MM-LOCK"))
    )
  )
  (nets
    (net (code "1") (name "+3V3") (class "Default")
      (node (ref "C11") (pin "1") (pinfunction "1_1") (pintype "passive"))
      (node (ref "C4") (pin "1") (pinfunction "1_1") (pintype "passive"))
      (node (ref "R1") (pin "2") (pinfunction "2_2") (pintype "passive"))
      (node (ref "R45") (pin "1") (pinfunction "1_1") (pintype "passive"))
      (node (ref "R46") (pin "1") (pinfunction "1_1") (pintype "passive"))
      (node (ref "R47") (pin "1") (pinfunction "1_1") (pintype "passive"))
      (node (ref "R48") (pin "1") (pinfunction "1_1") (pintype "passive"))
      (node (ref "R49") (pin "1") (pinfunction "1_1") (pintype "passive"))
      (node (ref "R50") (pin "1") (pinfunction "1_1") (pintype "passive"))
      (node (ref "R51") (pin "1") (pinfunction "1_1") (pintype "passive"))
      (node (ref "R52") (pin "1") (pinfunction "1_1") (pintype "passive"))
      (node (ref "R53") (pin "1") (pinfunction "1_1") (pintype "passive"))
      (node (ref "R54") (pin "1") (pinfunction "1_1") (pintype "passive"))
      (node (ref "R55") (pin "1") (pinfunction "1_1") (pintype "passive"))
      (node (ref "R56") (pin "1") (pinfunction "1_1") (pintype "passive"))
      (node (ref "R57") (pin "1") (pinfunction "1_1") (pintype "passive"))
      (node (ref "R58") (pin "1") (pinfunction "1_1") (pintype "passive"))
      (node (ref "R59") (pin "1") (pinfunction "1_1") (pintype "passive"))
      (node (ref "R60") (pin "1") (pinfunction "1_1") (pintype "passive"))
      (node (ref "RN2") (pin "1") (pinfunction "1_1") (pintype "passive"))
      (node (ref "RN4") (pin "1") (pinfunction "1_1") (pintype "passive"))
      (node (ref "SJ18") (pin "P$1") (pinfunction "1_P$1") (pintype "passive"))
      (node (ref "U$1") (pin "3V3") (pinfunction "3V3_3V3") (pintype "power_in"))
      (node (ref "U1") (pin "1") (pinfunction "SER_1") (pintype "input"))
      (node (ref "U1") (pin "16") (pinfunction "VCC_16") (pintype "power_in"))
      (node (ref "U1") (pin "9") (pinfunction "CLR_9") (pintype "input"))
      (node (ref "U2") (pin "16") (pinfunction "VCC_16") (pintype "power_in"))
      (node (ref "U2") (pin "9") (pinfunction "CLR_9") (pintype "input"))
    )
    (net (code "2") (name "+5V") (class "Default")
      (node (ref "C3") (pin "1") (pinfunction "1_1") (pintype "passive"))
      (node (ref "C5") (pin "1") (pinfunction "1_1") (pintype "passive"))
      (node (ref "C8") (pin "1") (pinfunction "1_1") (pintype "passive"))
      (node (ref "C9") (pin "1") (pinfunction "1_1") (pintype "passive"))
      (node (ref "JP1") (pin "3") (pinfunction "3_3") (pintype "passive"))
      (node (ref "JP2") (pin "6") (pinfunction "6_6") (pintype "passive"))
      (node (ref "JP5") (pin "3") (pinfunction "3_3") (pintype "passive"))
      (node (ref "JP5") (pin "4") (pinfunction "4_4") (pintype "passive"))
      (node (ref "JP6") (pin "3") (pinfunction "3_3") (pintype "passive"))
      (node (ref "JP6") (pin "4") (pinfunction "4_4") (pintype "passive"))
      (node (ref "JP7") (pin "3") (pinfunction "3_3") (pintype "passive"))
      (node (ref "JP7") (pin "4") (pinfunction "4_4") (pintype "passive"))
      (node (ref "JP8") (pin "3") (pinfunction "3_3") (pintype "passive"))
      (node (ref "JP8") (pin "4") (pinfunction "4_4") (pintype "passive"))
      (node (ref "PORTA") (pin "6") (pinfunction "6_6") (pintype "passive"))
      (node (ref "PORTB") (pin "6") (pinfunction "6_6") (pintype "passive"))
      (node (ref "PORTC") (pin "6") (pinfunction "6_6") (pintype "passive"))
      (node (ref "R19") (pin "2") (pinfunction "2_2") (pintype "passive"))
      (node (ref "R20") (pin "2") (pinfunction "2_2") (pintype "passive"))
      (node (ref "R21") (pin "2") (pinfunction "2_2") (pintype "passive"))
      (node (ref "R22") (pin "1") (pinfunction "1_1") (pintype "passive"))
      (node (ref "R23") (pin "1") (pinfunction "1_1") (pintype "passive"))
      (node (ref "R24") (pin "1") (pinfunction "1_1") (pintype "passive"))
      (node (ref "R25") (pin "1") (pinfunction "1_1") (pintype "passive"))
      (node (ref "R26") (pin "1") (pinfunction "1_1") (pintype "passive"))
      (node (ref "R27") (pin "1") (pinfunction "1_1") (pintype "passive"))
      (node (ref "R62") (pin "1") (pinfunction "1_1") (pintype "passive"))
      (node (ref "R63") (pin "1") (pinfunction "1_1") (pintype "passive"))
      (node (ref "R64") (pin "1") (pinfunction "1_1") (pintype "passive"))
      (node (ref "R65") (pin "1") (pinfunction "1_1") (pintype "passive"))
      (node (ref "R66") (pin "1") (pinfunction "1_1") (pintype "passive"))
      (node (ref "R67") (pin "1") (pinfunction "1_1") (pintype "passive"))
      (node (ref "SJ1") (pin "P$2") (pinfunction "2_P$2") (pintype "passive"))
      (node (ref "SJ10") (pin "P$2") (pinfunction "2_P$2") (pintype "passive"))
      (node (ref "SJ4") (pin "P$2") (pinfunction "2_P$2") (pintype "passive"))
      (node (ref "SJ7") (pin "P$2") (pinfunction "2_P$2") (pintype "passive"))
      (node (ref "U$1") (pin "5V2") (pinfunction "5V2_5V2") (pintype "power_in"))
      (node (ref "U11") (pin "10") (pinfunction "SCL_10") (pintype "input"))
      (node (ref "U11") (pin "16") (pinfunction "VCC_16") (pintype "power_in"))
      (node (ref "U13") (pin "10") (pinfunction "SCL_10") (pintype "input"))
      (node (ref "U13") (pin "16") (pinfunction "VCC_16") (pintype "power_in"))
      (node (ref "U7") (pin "3") (pinfunction "VCC_3") (pintype "power_in"))
      (node (ref "U7B") (pin "3") (pinfunction "VDD_3") (pintype "power_in"))
      (node (ref "X6") (pin "1") (pinfunction "1_1") (pintype "passive"))
    )
    (net (code "3") (name "+12V") (class "Default")
      (node (ref "C10") (pin "1") (pinfunction "1_1") (pintype "passive"))
      (node (ref "C6") (pin "1") (pinfunction "1_1") (pintype "passive"))
      (node (ref "C7") (pin "1") (pinfunction "1_1") (pintype "passive"))
      (node (ref "J3") (pin "1") (pinfunction "1_1") (pintype "passive"))
      (node (ref "JP2") (pin "7") (pinfunction "7_7") (pintype "passive"))
      (node (ref "JP4") (pin "2") (pinfunction "2_2") (pintype "passive"))
      (node (ref "SJ11") (pin "P$2") (pinfunction "2_P$2") (pintype "passive"))
      (node (ref "SJ14") (pin "P$2") (pinfunction "2_P$2") (pintype "passive"))
      (node (ref "SJ2") (pin "P$2") (pinfunction "2_P$2") (pintype "passive"))
      (node (ref "SJ5") (pin "P$2") (pinfunction "2_P$2") (pintype "passive"))
      (node (ref "SJ8") (pin "P$2") (pinfunction "2_P$2") (pintype "passive"))
      (node (ref "U10") (pin "4") (pinfunction "V+_4") (pintype "power_in"))
      (node (ref "U3") (pin "6") (pinfunction "VDD_6") (pintype "power_in"))
      (node (ref "U4") (pin "6") (pinfunction "VDD_6") (pintype "power_in"))
      (node (ref "U5") (pin "6") (pinfunction "VDD_6") (pintype "power_in"))
      (node (ref "U6") (pin "6") (pinfunction "VDD_6") (pintype "power_in"))
      (node (ref "U8") (pin "1") (pinfunction "VIN_1") (pintype "bidirectional"))
      (node (ref "U8B") (pin "5") (pinfunction "IN_5") (pintype "input"))
      (node (ref "U9") (pin "4") (pinfunction "V+_4") (pintype "power_in"))
    )
    (net (code "4") (name "/AGND") (class "Default")
      (node (ref "U$1") (pin "AGND") (pinfunction "AGND_AGND") (pintype "power_in"))
    )
    (net (code "5") (name "/AVDD") (class "Default")
      (node (ref "U$1") (pin "AVDD") (pinfunction "AVDD_AVDD") (pintype "power_in"))
    )
    (net (code "6") (name "/CANH") (class "Default")
      (node (ref "J1") (pin "1") (pinfunction "1_1") (pintype "passive"))
      (node (ref "J2") (pin "1") (pinfunction "1_1") (pintype "passive"))
      (node (ref "U7") (pin "7") (pinfunction "CANH_7") (pintype "bidirectional"))
      (node (ref "U7B") (pin "7") (pinfunction "CANH_7") (pintype "bidirectional"))
    )
    (net (code "7") (name "/CANL") (class "Default")
      (node (ref "J1") (pin "2") (pinfunction "2_2") (pintype "passive"))
      (node (ref "J2") (pin "2") (pinfunction "2_2") (pintype "passive"))
      (node (ref "U7") (pin "6") (pinfunction "CANL_6") (pintype "bidirectional"))
      (node (ref "U7B") (pin "6") (pinfunction "CANL_6") (pintype "bidirectional"))
    )
    (net (code "8") (name "/GND4") (class "Default")
      (node (ref "U$1") (pin "GND4") (pinfunction "GND4_GND4") (pintype "power_in"))
    )
    (net (code "9") (name "/PWR_POS") (class "Default")
      (node (ref "J1") (pin "8") (pinfunction "8_8") (pintype "passive"))
      (node (ref "J2") (pin "8") (pinfunction "8_8") (pintype "passive"))
      (node (ref "R40") (pin "2") (pinfunction "2_2") (pintype "passive"))
    )
    (net (code "10") (name "/U5V") (class "Default")
      (node (ref "U$1") (pin "U5V") (pinfunction "U5V_U5V") (pintype "power_in"))
    )
    (net (code "11") (name "/VBAT") (class "Default")
      (node (ref "U$1") (pin "VBAT") (pinfunction "VBAT_VBAT") (pintype "power_in"))
    )
    (net (code "12") (name "/VDD") (class "Default")
      (node (ref "U$1") (pin "VDD") (pinfunction "VDD_VDD") (pintype "power_in"))
    )
    (net (code "13") (name "CANRX") (class "Default")
      (node (ref "U$1") (pin "PB8") (pinfunction "PB8_PB8") (pintype "bidirectional"))
      (node (ref "U7") (pin "4") (pinfunction "RXD_4") (pintype "output"))
      (node (ref "U7B") (pin "4") (pinfunction "RXD_4") (pintype "bidirectional"))
    )
    (net (code "14") (name "CANTX") (class "Default")
      (node (ref "U$1") (pin "PB9") (pinfunction "PB9_PB9") (pintype "bidirectional"))
      (node (ref "U7") (pin "1") (pinfunction "TXD_1") (pintype "input"))
      (node (ref "U7B") (pin "1") (pinfunction "TXD_1") (pintype "bidirectional"))
    )
    (net (code "15") (name "E_CS") (class "Default")
      (node (ref "JP2") (pin "4") (pinfunction "4_4") (pintype "passive"))
      (node (ref "R23") (pin "2") (pinfunction "2_2") (pintype "passive"))
      (node (ref "U$1") (pin "PC10") (pinfunction "PC10_PC10") (pintype "bidirectional"))
    )
    (net (code "16") (name "E_LAT") (class "Default")
      (node (ref "JP2") (pin "5") (pinfunction "5_5") (pintype "passive"))
      (node (ref "R22") (pin "2") (pinfunction "2_2") (pintype "passive"))
      (node (ref "U$1") (pin "PC11") (pinfunction "PC11_PC11") (pintype "bidirectional"))
    )
    (net (code "17") (name "GND") (class "Default")
      (node (ref "C1") (pin "2") (pinfunction "2_2") (pintype "passive"))
      (node (ref "C10") (pin "2") (pinfunction "2_2") (pintype "passive"))
      (node (ref "C11") (pin "2") (pinfunction "2_2") (pintype "passive"))
      (node (ref "C2") (pin "-") (pinfunction "-_-") (pintype "passive"))
      (node (ref "C3") (pin "2") (pinfunction "2_2") (pintype "passive"))
      (node (ref "C4") (pin "2") (pinfunction "2_2") (pintype "passive"))
      (node (ref "C5") (pin "2") (pinfunction "2_2") (pintype "passive"))
      (node (ref "C6") (pin "2") (pinfunction "2_2") (pintype "passive"))
      (node (ref "C7") (pin "2") (pinfunction "2_2") (pintype "passive"))
      (node (ref "C8") (pin "2") (pinfunction "2_2") (pintype "passive"))
      (node (ref "C9") (pin "2") (pinfunction "2_2") (pintype "passive"))
      (node (ref "D1") (pin "A") (pinfunction "A_A") (pintype "passive"))
      (node (ref "D3") (pin "A") (pinfunction "A_A") (pintype "passive"))
      (node (ref "J1") (pin "3") (pinfunction "3_3") (pintype "passive"))
      (node (ref "J1") (pin "6") (pinfunction "6_6") (pintype "passive"))
      (node (ref "J1") (pin "7") (pinfunction "7_7") (pintype "passive"))
      (node (ref "J2") (pin "3") (pinfunction "3_3") (pintype "passive"))
      (node (ref "J2") (pin "6") (pinfunction "6_6") (pintype "passive"))
      (node (ref "J2") (pin "7") (pinfunction "7_7") (pintype "passive"))
      (node (ref "J3") (pin "2") (pinfunction "2_2") (pintype "passive"))
      (node (ref "J3") (pin "3") (pinfunction "3_3") (pintype "passive"))
      (node (ref "JP1") (pin "4") (pinfunction "4_4") (pintype "passive"))
      (node (ref "JP2") (pin "8") (pinfunction "8_8") (pintype "passive"))
      (node (ref "JP5") (pin "5") (pinfunction "5_5") (pintype "passive"))
      (node (ref "JP5") (pin "6") (pinfunction "6_6") (pintype "passive"))
      (node (ref "JP6") (pin "5") (pinfunction "5_5") (pintype "passive"))
      (node (ref "JP6") (pin "6") (pinfunction "6_6") (pintype "passive"))
      (node (ref "JP7") (pin "5") (pinfunction "5_5") (pintype "passive"))
      (node (ref "JP7") (pin "6") (pinfunction "6_6") (pintype "passive"))
      (node (ref "JP8") (pin "5") (pinfunction "5_5") (pintype "passive"))
      (node (ref "JP8") (pin "6") (pinfunction "6_6") (pintype "passive"))
      (node (ref "PORTA") (pin "5") (pinfunction "5_5") (pintype "passive"))
      (node (ref "PORTB") (pin "5") (pinfunction "5_5") (pintype "passive"))
      (node (ref "PORTC") (pin "5") (pinfunction "5_5") (pintype "passive"))
      (node (ref "Q1") (pin "2") (pinfunction "S_2") (pintype "passive"))
      (node (ref "Q10") (pin "2") (pinfunction "S_2") (pintype "passive"))
      (node (ref "Q11") (pin "2") (pinfunction "S_2") (pintype "passive"))
      (node (ref "Q12") (pin "2") (pinfunction "S_2") (pintype "passive"))
      (node (ref "Q13") (pin "2") (pinfunction "S_2") (pintype "passive"))
      (node (ref "Q14") (pin "2") (pinfunction "S_2") (pintype "passive"))
      (node (ref "Q15") (pin "2") (pinfunction "S_2") (pintype "passive"))
      (node (ref "Q16") (pin "2") (pinfunction "S_2") (pintype "passive"))
      (node (ref "Q2") (pin "2") (pinfunction "S_2") (pintype "passive"))
      (node (ref "Q3") (pin "2") (pinfunction "S_2") (pintype "passive"))
      (node (ref "Q4") (pin "2") (pinfunction "S_2") (pintype "passive"))
      (node (ref "Q5") (pin "2") (pinfunction "S_2") (pintype "passive"))
      (node (ref "Q6") (pin "2") (pinfunction "S_2") (pintype "passive"))
      (node (ref "Q7") (pin "2") (pinfunction "S_2") (pintype "passive"))
      (node (ref "Q8") (pin "2") (pinfunction "S_2") (pintype "passive"))
      (node (ref "Q9") (pin "2") (pinfunction "S_2") (pintype "passive"))
      (node (ref "R2") (pin "1") (pinfunction "1_1") (pintype "passive"))
      (node (ref "R61") (pin "2") (pinfunction "2_2") (pintype "passive"))
      (node (ref "SJ12") (pin "P$2") (pinfunction "2_P$2") (pintype "passive"))
      (node (ref "SJ3") (pin "2") (pinfunction "2_2") (pintype "passive"))
      (node (ref "SJ6") (pin "P$2") (pinfunction "2_P$2") (pintype "passive"))
      (node (ref "SJ9") (pin "2") (pinfunction "2_2") (pintype "passive"))
      (node (ref "U$1") (pin "GND3") (pinfunction "GND3_GND3") (pintype "power_in"))
      (node (ref "U$1") (pin "GND5") (pinfunction "GND5_GND5") (pintype "power_in"))
      (node (ref "U$1") (pin "GND6") (pinfunction "GND6_GND6") (pintype "power_in"))
      (node (ref "U$1") (pin "GND7") (pinfunction "GND7_GND7") (pintype "power_in"))
      (node (ref "U$1") (pin "GND8") (pinfunction "GND8_GND8") (pintype "power_in"))
      (node (ref "U1") (pin "6") (pinfunction "INH_6") (pintype "input"))
      (node (ref "U1") (pin "8") (pinfunction "GND_8") (pintype "power_in"))
      (node (ref "U10") (pin "11") (pinfunction "V-_11") (pintype "power_in"))
      (node (ref "U11") (pin "13") (pinfunction "G_13") (pintype "input"))
      (node (ref "U11") (pin "8") (pinfunction "GND_8") (pintype "power_in"))
      (node (ref "U13") (pin "13") (pinfunction "G_13") (pintype "input"))
      (node (ref "U13") (pin "8") (pinfunction "GND_8") (pintype "power_in"))
      (node (ref "U2") (pin "6") (pinfunction "INH_6") (pintype "input"))
      (node (ref "U2") (pin "8") (pinfunction "GND_8") (pintype "power_in"))
      (node (ref "U3") (pin "3") (pinfunction "VSS_3") (pintype "power_in"))
      (node (ref "U4") (pin "3") (pinfunction "VSS_3") (pintype "power_in"))
      (node (ref "U5") (pin "3") (pinfunction "VSS_3") (pintype "power_in"))
      (node (ref "U6") (pin "3") (pinfunction "VSS_3") (pintype "power_in"))
      (node (ref "U7") (pin "2") (pinfunction "GND_2") (pintype "power_in"))
      (node (ref "U7B") (pin "2") (pinfunction "VSS_2") (pintype "power_in"))
      (node (ref "U8") (pin "4") (pinfunction "SD_4") (pintype "bidirectional"))
      (node (ref "U8") (pin "5") (pinfunction "GND1_5") (pintype "power_in"))
      (node (ref "U8") (pin "6") (pinfunction "GND2_6") (pintype "power_in"))
      (node (ref "U8") (pin "7") (pinfunction "GND3_7") (pintype "power_in"))
      (node (ref "U8") (pin "8") (pinfunction "GND4_8") (pintype "power_in"))
      (node (ref "U8B") (pin "2") (pinfunction "GNDSIG_2") (pintype "input"))
      (node (ref "U8B") (pin "3") (pinfunction "~{ON/OFF}_3") (pintype "input"))
      (node (ref "U8B") (pin "4") (pinfunction "GND_4") (pintype "power_in"))
      (node (ref "U9") (pin "11") (pinfunction "V-_11") (pintype "power_in"))
      (node (ref "X6") (pin "2") (pinfunction "2_2") (pintype "passive"))
    )
    (net (code "18") (name "I2CSCL") (class "Default")
      (node (ref "JP1") (pin "1") (pinfunction "1_1") (pintype "passive"))
      (node (ref "R62") (pin "2") (pinfunction "2_2") (pintype "passive"))
      (node (ref "U$1") (pin "PB6") (pinfunction "PB6_PB6") (pintype "bidirectional"))
    )
    (net (code "19") (name "I2CSDA") (class "Default")
      (node (ref "JP1") (pin "2") (pinfunction "2_2") (pintype "passive"))
      (node (ref "R63") (pin "2") (pinfunction "2_2") (pintype "passive"))
      (node (ref "U$1") (pin "PB7") (pinfunction "PB7_PB7") (pintype "bidirectional"))
    )
    (net (code "20") (name "ILAT") (class "Default")
      (node (ref "U$1") (pin "PA6") (pinfunction "PA6_PA6") (pintype "bidirectional"))
      (node (ref "U1") (pin "15") (pinfunction "SH/~{LD}_15") (pintype "input"))
      (node (ref "U2") (pin "15") (pinfunction "SH/~{LD}_15") (pintype "input"))
    )
    (net (code "21") (name "MISO") (class "Default")
      (node (ref "JP2") (pin "1") (pinfunction "1_1") (pintype "passive"))
      (node (ref "U$1") (pin "PB4") (pinfunction "PB4_PB4") (pintype "bidirectional"))
    )
    (net (code "22") (name "MISO2") (class "Default")
      (node (ref "SJ13") (pin "P$2") (pinfunction "2_P$2") (pintype "passive"))
      (node (ref "SJ19") (pin "P$2") (pinfunction "2_P$2") (pintype "passive"))
      (node (ref "U$1") (pin "PC2") (pinfunction "PC2_PC2") (pintype "bidirectional"))
      (node (ref "U2") (pin "13") (pinfunction "QH_13") (pintype "output"))
    )
    (net (code "23") (name "MOSI") (class "Default")
      (node (ref "R20") (pin "1") (pinfunction "1_1") (pintype "passive"))
      (node (ref "SJ15") (pin "1") (pinfunction "1_1") (pintype "passive"))
      (node (ref "SJ17") (pin "P$2") (pinfunction "2_P$2") (pintype "passive"))
      (node (ref "U$1") (pin "PB5") (pinfunction "PB5_PB5") (pintype "bidirectional"))
      (node (ref "U11") (pin "14") (pinfunction "SER_14") (pintype "input"))
    )
    (net (code "24") (name "Net-(D2-PadA)") (class "Default")
      (node (ref "D2") (pin "A") (pinfunction "A_A") (pintype "passive"))
      (node (ref "D4") (pin "A") (pinfunction "A_A") (pintype "passive"))
      (node (ref "JP4") (pin "4") (pinfunction "4_4") (pintype "passive"))
    )
    (net (code "25") (name "Net-(D2-PadC)") (class "Default")
      (node (ref "D2") (pin "C") (pinfunction "C_C") (pintype "passive"))
      (node (ref "D4") (pin "C") (pinfunction "C_C") (pintype "passive"))
      (node (ref "JP4") (pin "1") (pinfunction "1_1") (pintype "passive"))
    )
    (net (code "26") (name "Net-(J1-Pad4)") (class "Default")
      (node (ref "J1") (pin "4") (pinfunction "4_4") (pintype "passive"))
      (node (ref "J2") (pin "4") (pinfunction "4_4") (pintype "passive"))
    )
    (net (code "27") (name "Net-(J1-Pad5)") (class "Default")
      (node (ref "J1") (pin "5") (pinfunction "5_5") (pintype "passive"))
      (node (ref "J2") (pin "5") (pinfunction "5_5") (pintype "passive"))
    )
    (net (code "28") (name "Net-(JP4-Pad3)") (class "Default")
      (node (ref "JP4") (pin "3") (pinfunction "3_3") (pintype "passive"))
      (node (ref "R40") (pin "1") (pinfunction "1_1") (pintype "passive"))
    )
    (net (code "29") (name "Net-(PORTA-Pad1)") (class "Default")
      (node (ref "PORTA") (pin "1") (pinfunction "1_1") (pintype "passive"))
      (node (ref "R44") (pin "2") (pinfunction "2_2") (pintype "passive"))
      (node (ref "R53") (pin "2") (pinfunction "2_2") (pintype "passive"))
      (node (ref "RN3") (pin "1") (pinfunction "1_1") (pintype "passive"))
      (node (ref "RN4") (pin "9") (pinfunction "9_9") (pintype "passive"))
      (node (ref "X1") (pin "1") (pinfunction "1_1") (pintype "passive"))
    )
    (net (code "30") (name "Net-(PORTB-Pad1)") (class "Default")
      (node (ref "PORTB") (pin "1") (pinfunction "1_1") (pintype "passive"))
      (node (ref "R35") (pin "2") (pinfunction "2_2") (pintype "passive"))
      (node (ref "R45") (pin "2") (pinfunction "2_2") (pintype "passive"))
      (node (ref "RN1") (pin "1") (pinfunction "1_1") (pintype "passive"))
      (node (ref "RN2") (pin "9") (pinfunction "9_9") (pintype "passive"))
      (node (ref "X2") (pin "1") (pinfunction "1_1") (pintype "passive"))
    )
    (net (code "31") (name "Net-(Q1-D)") (class "Default")
      (node (ref "Q1") (pin "3") (pinfunction "D_3") (pintype "passive"))
      (node (ref "U12") (pin "18") (pinfunction "O1_18") (pintype "open_collector"))
      (node (ref "X5") (pin "1") (pinfunction "1_1") (pintype "passive"))
    )
    (net (code "32") (name "Net-(Q1-G)") (class "Default")
      (node (ref "Q1") (pin "1") (pinfunction "G_1") (pintype "passive"))
      (node (ref "R3") (pin "2") (pinfunction "2_2") (pintype "passive"))
    )
    (net (code "33") (name "Net-(Q2-D)") (class "Default")
      (node (ref "Q2") (pin "3") (pinfunction "D_3") (pintype "passive"))
      (node (ref "U12") (pin "17") (pinfunction "O2_17") (pintype "open_collector"))
      (node (ref "X5") (pin "2") (pinfunction "2_2") (pintype "passive"))
    )
    (net (code "34") (name "Net-(Q2-G)") (class "Default")
      (node (ref "Q2") (pin "1") (pinfunction "G_1") (pintype "passive"))
      (node (ref "R4") (pin "2") (pinfunction "2_2") (pintype "passive"))
    )
    (net (code "35") (name "Net-(Q3-D)") (class "Default")
      (node (ref "Q3") (pin "3") (pinfunction "D_3") (pintype "passive"))
      (node (ref "U12") (pin "16") (pinfunction "O3_16") (pintype "open_collector"))
      (node (ref "X5") (pin "3") (pinfunction "3_3") (pintype "passive"))
    )
    (net (code "36") (name "Net-(Q3-G)") (class "Default")
      (node (ref "Q3") (pin "1") (pinfunction "G_1") (pintype "passive"))
      (node (ref "R5") (pin "2") (pinfunction "2_2") (pintype "passive"))
    )
    (net (code "37") (name "Net-(Q4-D)") (class "Default")
      (node (ref "Q4") (pin "3") (pinfunction "D_3") (pintype "passive"))
      (node (ref "U12") (pin "15") (pinfunction "O4_15") (pintype "open_collector"))
      (node (ref "X5") (pin "4") (pinfunction "4_4") (pintype "passive"))
    )
    (net (code "38") (name "Net-(Q4-G)") (class "Default")
      (node (ref "Q4") (pin "1") (pinfunction "G_1") (pintype "passive"))
      (node (ref "R6") (pin "2") (pinfunction "2_2") (pintype "passive"))
    )
    (net (code "39") (name "Net-(Q5-D)") (class "Default")
      (node (ref "Q5") (pin "3") (pinfunction "D_3") (pintype "passive"))
      (node (ref "U12") (pin "14") (pinfunction "O5_14") (pintype "open_collector"))
      (node (ref "X5") (pin "5") (pinfunction "5_5") (pintype "passive"))
    )
    (net (code "40") (name "Net-(Q5-G)") (class "Default")
      (node (ref "Q5") (pin "1") (pinfunction "G_1") (pintype "passive"))
      (node (ref "R7") (pin "2") (pinfunction "2_2") (pintype "passive"))
    )
    (net (code "41") (name "Net-(Q6-D)") (class "Default")
      (node (ref "Q6") (pin "3") (pinfunction "D_3") (pintype "passive"))
      (node (ref "U12") (pin "13") (pinfunction "O6_13") (pintype "open_collector"))
      (node (ref "X5") (pin "6") (pinfunction "6_6") (pintype "passive"))
    )
    (net (code "42") (name "Net-(Q6-G)") (class "Default")
      (node (ref "Q6") (pin "1") (pinfunction "G_1") (pintype "passive"))
      (node (ref "R8") (pin "2") (pinfunction "2_2") (pintype "passive"))
    )
    (net (code "43") (name "Net-(Q7-D)") (class "Default")
      (node (ref "Q7") (pin "3") (pinfunction "D_3") (pintype "passive"))
      (node (ref "U12") (pin "12") (pinfunction "O7_12") (pintype "open_collector"))
      (node (ref "X5") (pin "7") (pinfunction "7_7") (pintype "passive"))
    )
    (net (code "44") (name "Net-(Q7-G)") (class "Default")
      (node (ref "Q7") (pin "1") (pinfunction "G_1") (pintype "passive"))
      (node (ref "R9") (pin "2") (pinfunction "2_2") (pintype "passive"))
    )
    (net (code "45") (name "Net-(Q8-D)") (class "Default")
      (node (ref "Q8") (pin "3") (pinfunction "D_3") (pintype "passive"))
      (node (ref "U12") (pin "11") (pinfunction "O8_11") (pintype "open_collector"))
      (node (ref "X5") (pin "8") (pinfunction "8_8") (pintype "passive"))
    )
    (net (code "46") (name "Net-(Q8-G)") (class "Default")
      (node (ref "Q8") (pin "1") (pinfunction "G_1") (pintype "passive"))
      (node (ref "R10") (pin "2") (pinfunction "2_2") (pintype "passive"))
    )
    (net (code "47") (name "Net-(Q9-D)") (class "Default")
      (node (ref "Q9") (pin "3") (pinfunction "D_3") (pintype "passive"))
      (node (ref "U14") (pin "18") (pinfunction "O1_18") (pintype "open_collector"))
      (node (ref "X4") (pin "1") (pinfunction "1_1") (pintype "passive"))
    )
    (net (code "48") (name "Net-(Q9-G)") (class "Default")
      (node (ref "Q9") (pin "1") (pinfunction "G_1") (pintype "passive"))
      (node (ref "R11") (pin "2") (pinfunction "2_2") (pintype "passive"))
    )
    (net (code "49") (name "Net-(Q10-D)") (class "Default")
      (node (ref "Q10") (pin "3") (pinfunction "D_3") (pintype "passive"))
      (node (ref "U14") (pin "17") (pinfunction "O2_17") (pintype "open_collector"))
      (node (ref "X4") (pin "2") (pinfunction "2_2") (pintype "passive"))
    )
    (net (code "50") (name "Net-(Q10-G)") (class "Default")
      (node (ref "Q10") (pin "1") (pinfunction "G_1") (pintype "passive"))
      (node (ref "R12") (pin "2") (pinfunction "2_2") (pintype "passive"))
    )
    (net (code "51") (name "Net-(Q11-D)") (class "Default")
      (node (ref "Q11") (pin "3") (pinfunction "D_3") (pintype "passive"))
      (node (ref "U14") (pin "16") (pinfunction "O3_16") (pintype "open_collector"))
      (node (ref "X4") (pin "3") (pinfunction "3_3") (pintype "passive"))
    )
    (net (code "52") (name "Net-(Q11-G)") (class "Default")
      (node (ref "Q11") (pin "1") (pinfunction "G_1") (pintype "passive"))
      (node (ref "R13") (pin "2") (pinfunction "2_2") (pintype "passive"))
    )
    (net (code "53") (name "Net-(Q12-D)") (class "Default")
      (node (ref "Q12") (pin "3") (pinfunction "D_3") (pintype "passive"))
      (node (ref "U14") (pin "15") (pinfunction "O4_15") (pintype "open_collector"))
      (node (ref "X4") (pin "4") (pinfunction "4_4") (pintype "passive"))
    )
    (net (code "54") (name "Net-(Q12-G)") (class "Default")
      (node (ref "Q12") (pin "1") (pinfunction "G_1") (pintype "passive"))
      (node (ref "R14") (pin "2") (pinfunction "2_2") (pintype "passive"))
    )
    (net (code "55") (name "Net-(Q13-D)") (class "Default")
      (node (ref "Q13") (pin "3") (pinfunction "D_3") (pintype "passive"))
      (node (ref "U14") (pin "14") (pinfunction "O5_14") (pintype "open_collector"))
      (node (ref "X4") (pin "5") (pinfunction "5_5") (pintype "passive"))
    )
    (net (code "56") (name "Net-(Q13-G)") (class "Default")
      (node (ref "Q13") (pin "1") (pinfunction "G_1") (pintype "passive"))
      (node (ref "R15") (pin "2") (pinfunction "2_2") (pintype "passive"))
    )
    (net (code "57") (name "Net-(Q14-D)") (class "Default")
      (node (ref "Q14") (pin "3") (pinfunction "D_3") (pintype "passive"))
      (node (ref "U14") (pin "13") (pinfunction "O6_13") (pintype "open_collector"))
      (node (ref "X4") (pin "6") (pinfunction "6_6") (pintype "passive"))
    )
    (net (code "58") (name "Net-(Q14-G)") (class "Default")
      (node (ref "Q14") (pin "1") (pinfunction "G_1") (pintype "passive"))
      (node (ref "R16") (pin "2") (pinfunction "2_2") (pintype "passive"))
    )
    (net (code "59") (name "Net-(Q15-D)") (class "Default")
      (node (ref "Q15") (pin "3") (pinfunction "D_3") (pintype "passive"))
      (node (ref "U14") (pin "12") (pinfunction "O7_12") (pintype "open_collector"))
      (node (ref "X4") (pin "7") (pinfunction "7_7") (pintype "passive"))
    )
    (net (code "60") (name "Net-(Q15-G)") (class "Default")
      (node (ref "Q15") (pin "1") (pinfunction "G_1") (pintype "passive"))
      (node (ref "R17") (pin "2") (pinfunction "2_2") (pintype "passive"))
    )
    (net (code "61") (name "Net-(Q16-D)") (class "Default")
      (node (ref "Q16") (pin "3") (pinfunction "D_3") (pintype "passive"))
      (node (ref "U14") (pin "11") (pinfunction "O8_11") (pintype "open_collector"))
      (node (ref "X4") (pin "8") (pinfunction "8_8") (pintype "passive"))
    )
    (net (code "62") (name "Net-(Q16-G)") (class "Default")
      (node (ref "Q16") (pin "1") (pinfunction "G_1") (pintype "passive"))
      (node (ref "R18") (pin "2") (pinfunction "2_2") (pintype "passive"))
    )
    (net (code "63") (name "Net-(RN1A-2)") (class "Default")
      (node (ref "R35") (pin "1") (pinfunction "1_1") (pintype "passive"))
      (node (ref "RN1") (pin "16") (pinfunction "2_16") (pintype "passive"))
      (node (ref "U2") (pin "14") (pinfunction "H_14") (pintype "input"))
    )
    (net (code "64") (name "Net-(RN1B-1)") (class "Default")
      (node (ref "PORTB") (pin "2") (pinfunction "2_2") (pintype "passive"))
      (node (ref "R34") (pin "2") (pinfunction "2_2") (pintype "passive"))
      (node (ref "R46") (pin "2") (pinfunction "2_2") (pintype "passive"))
      (node (ref "RN1") (pin "2") (pinfunction "1_2") (pintype "passive"))
      (node (ref "RN2") (pin "8") (pinfunction "8_8") (pintype "passive"))
      (node (ref "X2") (pin "2") (pinfunction "2_2") (pintype "passive"))
    )
    (net (code "65") (name "Net-(RN1B-2)") (class "Default")
      (node (ref "R34") (pin "1") (pinfunction "1_1") (pintype "passive"))
      (node (ref "RN1") (pin "15") (pinfunction "2_15") (pintype "passive"))
      (node (ref "U2") (pin "12") (pinfunction "G_12") (pintype "input"))
    )
    (net (code "66") (name "Net-(RN1C-1)") (class "Default")
      (node (ref "PORTB") (pin "3") (pinfunction "3_3") (pintype "passive"))
      (node (ref "R33") (pin "2") (pinfunction "2_2") (pintype "passive"))
      (node (ref "R47") (pin "2") (pinfunction "2_2") (pintype "passive"))
      (node (ref "RN1") (pin "3") (pinfunction "1_3") (pintype "passive"))
      (node (ref "RN2") (pin "7") (pinfunction "7_7") (pintype "passive"))
      (node (ref "X2") (pin "3") (pinfunction "3_3") (pintype "passive"))
    )
    (net (code "67") (name "Net-(RN1C-2)") (class "Default")
      (node (ref "R33") (pin "1") (pinfunction "1_1") (pintype "passive"))
      (node (ref "RN1") (pin "14") (pinfunction "2_14") (pintype "passive"))
      (node (ref "U2") (pin "11") (pinfunction "F_11") (pintype "input"))
    )
    (net (code "68") (name "Net-(RN1D-1)") (class "Default")
      (node (ref "PORTB") (pin "4") (pinfunction "4_4") (pintype "passive"))
      (node (ref "R32") (pin "2") (pinfunction "2_2") (pintype "passive"))
      (node (ref "R48") (pin "2") (pinfunction "2_2") (pintype "passive"))
      (node (ref "RN1") (pin "4") (pinfunction "1_4") (pintype "passive"))
      (node (ref "RN2") (pin "6") (pinfunction "6_6") (pintype "passive"))
      (node (ref "X2") (pin "4") (pinfunction "4_4") (pintype "passive"))
    )
    (net (code "69") (name "Net-(RN1D-2)") (class "Default")
      (node (ref "R32") (pin "1") (pinfunction "1_1") (pintype "passive"))
      (node (ref "RN1") (pin "13") (pinfunction "2_13") (pintype "passive"))
      (node (ref "U2") (pin "10") (pinfunction "E_10") (pintype "input"))
    )
    (net (code "70") (name "Net-(RN1E-1)") (class "Default")
      (node (ref "PORTB") (pin "7") (pinfunction "7_7") (pintype "passive"))
      (node (ref "R31") (pin "2") (pinfunction "2_2") (pintype "passive"))
      (node (ref "R49") (pin "2") (pinfunction "2_2") (pintype "passive"))
      (node (ref "RN1") (pin "5") (pinfunction "1_5") (pintype "passive"))
      (node (ref "RN2") (pin "5") (pinfunction "5_5") (pintype "passive"))
      (node (ref "X2") (pin "5") (pinfunction "5_5") (pintype "passive"))
    )
    (net (code "71") (name "Net-(RN1E-2)") (class "Default")
      (node (ref "R31") (pin "1") (pinfunction "1_1") (pintype "passive"))
      (node (ref "RN1") (pin "12") (pinfunction "2_12") (pintype "passive"))
      (node (ref "U2") (pin "5") (pinfunction "D_5") (pintype "input"))
    )
    (net (code "72") (name "Net-(RN1F-1)") (class "Default")
      (node (ref "PORTB") (pin "8") (pinfunction "8_8") (pintype "passive"))
      (node (ref "R30") (pin "2") (pinfunction "2_2") (pintype "passive"))
      (node (ref "R50") (pin "2") (pinfunction "2_2") (pintype "passive"))
      (node (ref "RN1") (pin "6") (pinfunction "1_6") (pintype "passive"))
      (node (ref "RN2") (pin "4") (pinfunction "4_4") (pintype "passive"))
      (node (ref "X2") (pin "6") (pinfunction "6_6") (pintype "passive"))
    )
    (net (code "73") (name "Net-(RN1F-2)") (class "Default")
      (node (ref "R30") (pin "1") (pinfunction "1_1") (pintype "passive"))
      (node (ref "RN1") (pin "11") (pinfunction "2_11") (pintype "passive"))
      (node (ref "U2") (pin "4") (pinfunction "C_4") (pintype "input"))
    )
    (net (code "74") (name "Net-(RN1G-1)") (class "Default")
      (node (ref "PORTB") (pin "9") (pinfunction "9_9") (pintype "passive"))
      (node (ref "R29") (pin "2") (pinfunction "2_2") (pintype "passive"))
      (node (ref "R51") (pin "2") (pinfunction "2_2") (pintype "passive"))
      (node (ref "RN1") (pin "7") (pinfunction "1_7") (pintype "passive"))
      (node (ref "RN2") (pin "3") (pinfunction "3_3") (pintype "passive"))
      (node (ref "X2") (pin "7") (pinfunction "7_7") (pintype "passive"))
    )
    (net (code "75") (name "Net-(RN1G-2)") (class "Default")
      (node (ref "R29") (pin "1") (pinfunction "1_1") (pintype "passive"))
      (node (ref "RN1") (pin "10") (pinfunction "2_10") (pintype "passive"))
      (node (ref "U2") (pin "3") (pinfunction "B_3") (pintype "input"))
    )
    (net (code "76") (name "Net-(RN1H-1)") (class "Default")
      (node (ref "PORTB") (pin "10") (pinfunction "10_10") (pintype "passive"))
      (node (ref "R28") (pin "2") (pinfunction "2_2") (pintype "passive"))
      (node (ref "R52") (pin "2") (pinfunction "2_2") (pintype "passive"))
      (node (ref "RN1") (pin "8") (pinfunction "1_8") (pintype "passive"))
      (node (ref "RN2") (pin "2") (pinfunction "2_2") (pintype "passive"))
      (node (ref "X2") (pin "8") (pinfunction "8_8") (pintype "passive"))
    )
    (net (code "77") (name "Net-(RN1H-2)") (class "Default")
      (node (ref "R28") (pin "1") (pinfunction "1_1") (pintype "passive"))
      (node (ref "RN1") (pin "9") (pinfunction "2_9") (pintype "passive"))
      (node (ref "U2") (pin "2") (pinfunction "A_2") (pintype "input"))
    )
    (net (code "78") (name "Net-(RN3A-2)") (class "Default")
      (node (ref "R44") (pin "1") (pinfunction "1_1") (pintype "passive"))
      (node (ref "RN3") (pin "16") (pinfunction "2_16") (pintype "passive"))
      (node (ref "U1") (pin "14") (pinfunction "H_14") (pintype "input"))
    )
    (net (code "79") (name "Net-(RN3B-1)") (class "Default")
      (node (ref "PORTA") (pin "2") (pinfunction "2_2") (pintype "passive"))
      (node (ref "R43") (pin "2") (pinfunction "2_2") (pintype "passive"))
      (node (ref "R54") (pin "2") (pinfunction "2_2") (pintype "passive"))
      (node (ref "RN3") (pin "2") (pinfunction "1_2") (pintype "passive"))
      (node (ref "RN4") (pin "8") (pinfunction "8_8") (pintype "passive"))
      (node (ref "X1") (pin "2") (pinfunction "2_2") (pintype "passive"))
    )
    (net (code "80") (name "Net-(RN3B-2)") (class "Default")
      (node (ref "R43") (pin "1") (pinfunction "1_1") (pintype "passive"))
      (node (ref "RN3") (pin "15") (pinfunction "2_15") (pintype "passive"))
      (node (ref "U1") (pin "12") (pinfunction "G_12") (pintype "input"))
    )
    (net (code "81") (name "Net-(RN3C-1)") (class "Default")
      (node (ref "PORTA") (pin "3") (pinfunction "3_3") (pintype "passive"))
      (node (ref "R42") (pin "2") (pinfunction "2_2") (pintype "passive"))
      (node (ref "R55") (pin "2") (pinfunction "2_2") (pintype "passive"))
      (node (ref "RN3") (pin "3") (pinfunction "1_3") (pintype "passive"))
      (node (ref "RN4") (pin "7") (pinfunction "7_7") (pintype "passive"))
      (node (ref "X1") (pin "3") (pinfunction "3_3") (pintype "passive"))
    )
    (net (code "82") (name "Net-(RN3C-2)") (class "Default")
      (node (ref "R42") (pin "1") (pinfunction "1_1") (pintype "passive"))
      (node (ref "RN3") (pin "14") (pinfunction "2_14") (pintype "passive"))
      (node (ref "U1") (pin "11") (pinfunction "F_11") (pintype "input"))
    )
    (net (code "83") (name "Net-(RN3D-1)") (class "Default")
      (node (ref "PORTA") (pin "4") (pinfunction "4_4") (pintype "passive"))
      (node (ref "R41") (pin "2") (pinfunction "2_2") (pintype "passive"))
      (node (ref "R56") (pin "2") (pinfunction "2_2") (pintype "passive"))
      (node (ref "RN3") (pin "4") (pinfunction "1_4") (pintype "passive"))
      (node (ref "RN4") (pin "6") (pinfunction "6_6") (pintype "passive"))
      (node (ref "X1") (pin "4") (pinfunction "4_4") (pintype "passive"))
    )
    (net (code "84") (name "Net-(RN3D-2)") (class "Default")
      (node (ref "R41") (pin "1") (pinfunction "1_1") (pintype "passive"))
      (node (ref "RN3") (pin "13") (pinfunction "2_13") (pintype "passive"))
      (node (ref "U1") (pin "10") (pinfunction "E_10") (pintype "input"))
    )
    (net (code "85") (name "Net-(RN3E-1)") (class "Default")
      (node (ref "PORTA") (pin "7") (pinfunction "7_7") (pintype "passive"))
      (node (ref "R39") (pin "2") (pinfunction "2_2") (pintype "passive"))
      (node (ref "R57") (pin "2") (pinfunction "2_2") (pintype "passive"))
      (node (ref "RN3") (pin "5") (pinfunction "1_5") (pintype "passive"))
      (node (ref "RN4") (pin "5") (pinfunction "5_5") (pintype "passive"))
      (node (ref "X1") (pin "5") (pinfunction "5_5") (pintype "passive"))
    )
    (net (code "86") (name "Net-(RN3E-2)") (class "Default")
      (node (ref "R39") (pin "1") (pinfunction "1_1") (pintype "passive"))
      (node (ref "RN3") (pin "12") (pinfunction "2_12") (pintype "passive"))
      (node (ref "U1") (pin "5") (pinfunction "D_5") (pintype "input"))
    )
    (net (code "87") (name "Net-(RN3F-1)") (class "Default")
      (node (ref "PORTA") (pin "8") (pinfunction "8_8") (pintype "passive"))
      (node (ref "R38") (pin "2") (pinfunction "2_2") (pintype "passive"))
      (node (ref "R58") (pin "2") (pinfunction "2_2") (pintype "passive"))
      (node (ref "RN3") (pin "6") (pinfunction "1_6") (pintype "passive"))
      (node (ref "RN4") (pin "4") (pinfunction "4_4") (pintype "passive"))
      (node (ref "X1") (pin "6") (pinfunction "6_6") (pintype "passive"))
    )
    (net (code "88") (name "Net-(RN3F-2)") (class "Default")
      (node (ref "R38") (pin "1") (pinfunction "1_1") (pintype "passive"))
      (node (ref "RN3") (pin "11") (pinfunction "2_11") (pintype "passive"))
      (node (ref "U1") (pin "4") (pinfunction "C_4") (pintype "input"))
    )
    (net (code "89") (name "Net-(RN3G-1)") (class "Default")
      (node (ref "PORTA") (pin "9") (pinfunction "9_9") (pintype "passive"))
      (node (ref "R37") (pin "2") (pinfunction "2_2") (pintype "passive"))
      (node (ref "R59") (pin "2") (pinfunction "2_2") (pintype "passive"))
      (node (ref "RN3") (pin "7") (pinfunction "1_7") (pintype "passive"))
      (node (ref "RN4") (pin "3") (pinfunction "3_3") (pintype "passive"))
      (node (ref "X1") (pin "7") (pinfunction "7_7") (pintype "passive"))
    )
    (net (code "90") (name "Net-(RN3G-2)") (class "Default")
      (node (ref "R37") (pin "1") (pinfunction "1_1") (pintype "passive"))
      (node (ref "RN3") (pin "10") (pinfunction "2_10") (pintype "passive"))
      (node (ref "U1") (pin "3") (pinfunction "B_3") (pintype "input"))
    )
    (net (code "91") (name "Net-(RN3H-1)") (class "Default")
      (node (ref "PORTA") (pin "10") (pinfunction "10_10") (pintype "passive"))
      (node (ref "R36") (pin "2") (pinfunction "2_2") (pintype "passive"))
      (node (ref "R60") (pin "2") (pinfunction "2_2") (pintype "passive"))
      (node (ref "RN3") (pin "8") (pinfunction "1_8") (pintype "passive"))
      (node (ref "RN4") (pin "2") (pinfunction "2_2") (pintype "passive"))
      (node (ref "X1") (pin "8") (pinfunction "8_8") (pintype "passive"))
    )
    (net (code "92") (name "Net-(RN3H-2)") (class "Default")
      (node (ref "R36") (pin "1") (pinfunction "1_1") (pintype "passive"))
      (node (ref "RN3") (pin "9") (pinfunction "2_9") (pintype "passive"))
      (node (ref "U1") (pin "2") (pinfunction "A_2") (pintype "input"))
    )
    (net (code "93") (name "Net-(SJ1-1)") (class "Default")
      (node (ref "SJ1") (pin "P$1") (pinfunction "1_P$1") (pintype "passive"))
      (node (ref "SJ2") (pin "P$1") (pinfunction "1_P$1") (pintype "passive"))
      (node (ref "SJ3") (pin "1") (pinfunction "1_1") (pintype "passive"))
      (node (ref "U12") (pin "9") (pinfunction "GND_9") (pintype "power_in"))
    )
    (net (code "94") (name "Net-(SJ4-1)") (class "Default")
      (node (ref "SJ4") (pin "P$1") (pinfunction "1_P$1") (pintype "passive"))
      (node (ref "SJ5") (pin "P$1") (pinfunction "1_P$1") (pintype "passive"))
      (node (ref "SJ6") (pin "P$1") (pinfunction "1_P$1") (pintype "passive"))
      (node (ref "U12") (pin "10") (pinfunction "CD+_10") (pintype "passive"))
    )
    (net (code "95") (name "Net-(SJ7-1)") (class "Default")
      (node (ref "SJ7") (pin "P$1") (pinfunction "1_P$1") (pintype "passive"))
      (node (ref "SJ8") (pin "P$1") (pinfunction "1_P$1") (pintype "passive"))
      (node (ref "SJ9") (pin "1") (pinfunction "1_1") (pintype "passive"))
      (node (ref "U14") (pin "9") (pinfunction "GND_9") (pintype "power_in"))
    )
    (net (code "96") (name "Net-(SJ10-1)") (class "Default")
      (node (ref "SJ10") (pin "P$1") (pinfunction "1_P$1") (pintype "passive"))
      (node (ref "SJ11") (pin "P$1") (pinfunction "1_P$1") (pintype "passive"))
      (node (ref "SJ12") (pin "P$1") (pinfunction "1_P$1") (pintype "passive"))
      (node (ref "U14") (pin "10") (pinfunction "CD+_10") (pintype "passive"))
    )
    (net (code "97") (name "Net-(SJ13-1)") (class "Default")
      (node (ref "SJ13") (pin "P$1") (pinfunction "1_P$1") (pintype "passive"))
      (node (ref "U$1") (pin "PB14") (pinfunction "PB14_PB14") (pintype "bidirectional"))
    )
    (net (code "98") (name "Net-(SJ14-1)") (class "Default")
      (node (ref "SJ14") (pin "P$1") (pinfunction "1_P$1") (pintype "passive"))
      (node (ref "U$1") (pin "VIN2") (pinfunction "VIN2_VIN2") (pintype "power_in"))
    )
    (net (code "99") (name "Net-(SJ16-2)") (class "Default")
      (node (ref "JP2") (pin "2") (pinfunction "2_2") (pintype "passive"))
      (node (ref "SJ15") (pin "2") (pinfunction "2_2") (pintype "passive"))
      (node (ref "SJ16") (pin "P$2") (pinfunction "2_P$2") (pintype "passive"))
    )
    (net (code "100") (name "Net-(SJ18-2)") (class "Default")
      (node (ref "SJ18") (pin "P$2") (pinfunction "2_P$2") (pintype "passive"))
      (node (ref "U7") (pin "5") (pinfunction "VREF_5") (pintype "output"))
      (node (ref "U7B") (pin "5") (pinfunction "VREF_5") (pintype "bidirectional"))
    )
    (net (code "101") (name "Net-(U3A-O)") (class "Default")
      (node (ref "PORTC") (pin "1") (pinfunction "1_1") (pintype "passive"))
      (node (ref "U3") (pin "7") (pinfunction "O_7") (pintype "output"))
      (node (ref "U9") (pin "7") (pinfunction "OUT_7") (pintype "output"))
      (node (ref "X3") (pin "1") (pinfunction "1_1") (pintype "passive"))
    )
    (net (code "102") (name "Net-(U3B-O)") (class "Default")
      (node (ref "PORTC") (pin "2") (pinfunction "2_2") (pintype "passive"))
      (node (ref "U3") (pin "5") (pinfunction "O_5") (pintype "output"))
      (node (ref "U9") (pin "8") (pinfunction "OUT_8") (pintype "output"))
      (node (ref "X3") (pin "2") (pinfunction "2_2") (pintype "passive"))
    )
    (net (code "103") (name "Net-(U4A-O)") (class "Default")
      (node (ref "PORTC") (pin "4") (pinfunction "4_4") (pintype "passive"))
      (node (ref "U4") (pin "7") (pinfunction "O_7") (pintype "output"))
      (node (ref "U9") (pin "14") (pinfunction "OUT_14") (pintype "output"))
      (node (ref "X3") (pin "4") (pinfunction "4_4") (pintype "passive"))
    )
    (net (code "104") (name "Net-(U4B-O)") (class "Default")
      (node (ref "PORTC") (pin "3") (pinfunction "3_3") (pintype "passive"))
      (node (ref "U4") (pin "5") (pinfunction "O_5") (pintype "output"))
      (node (ref "U9") (pin "1") (pinfunction "OUT_1") (pintype "output"))
      (node (ref "X3") (pin "3") (pinfunction "3_3") (pintype "passive"))
    )
    (net (code "105") (name "Net-(U7-RS)") (class "Default")
      (node (ref "R61") (pin "1") (pinfunction "1_1") (pintype "passive"))
      (node (ref "U7") (pin "8") (pinfunction "RS_8") (pintype "input"))
      (node (ref "U7B") (pin "8") (pinfunction "RS_8") (pintype "bidirectional"))
    )
    (net (code "106") (name "Net-(U8-VOUT)") (class "Default")
      (node (ref "D1") (pin "C") (pinfunction "C_C") (pintype "passive"))
      (node (ref "D3") (pin "C") (pinfunction "C_C") (pintype "passive"))
      (node (ref "L1") (pin "2") (pinfunction "2_2") (pintype "passive"))
      (node (ref "U8") (pin "2") (pinfunction "VOUT_2") (pintype "bidirectional"))
      (node (ref "U8B") (pin "7") (pinfunction "OUT_7") (pintype "passive"))
    )
    (net (code "107") (name "Net-(U10A--IN)") (class "Default")
      (node (ref "R1") (pin "1") (pinfunction "1_1") (pintype "passive"))
      (node (ref "R2") (pin "2") (pinfunction "2_2") (pintype "passive"))
      (node (ref "U10") (pin "13") (pinfunction "-IN_13") (pintype "input"))
      (node (ref "U10") (pin "2") (pinfunction "-IN_2") (pintype "input"))
      (node (ref "U10") (pin "6") (pinfunction "-IN_6") (pintype "input"))
      (node (ref "U10") (pin "9") (pinfunction "-IN_9") (pintype "input"))
      (node (ref "U9") (pin "13") (pinfunction "-IN_13") (pintype "input"))
      (node (ref "U9") (pin "2") (pinfunction "-IN_2") (pintype "input"))
      (node (ref "U9") (pin "6") (pinfunction "-IN_6") (pintype "input"))
      (node (ref "U9") (pin "9") (pinfunction "-IN_9") (pintype "input"))
    )
    (net (code "108") (name "Net-(U10A-OUT)") (class "Default")
      (node (ref "PORTC") (pin "9") (pinfunction "9_9") (pintype "passive"))
      (node (ref "U10") (pin "1") (pinfunction "OUT_1") (pintype "output"))
      (node (ref "U6") (pin "5") (pinfunction "O_5") (pintype "output"))
      (node (ref "X3") (pin "7") (pinfunction "7_7") (pintype "passive"))
    )
    (net (code "109") (name "Net-(U10B-OUT)") (class "Default")
      (node (ref "PORTC") (pin "7") (pinfunction "7_7") (pintype "passive"))
      (node (ref "U10") (pin "7") (pinfunction "OUT_7") (pintype "output"))
      (node (ref "U5") (pin "7") (pinfunction "O_7") (pintype "output"))
      (node (ref "X3") (pin "5") (pinfunction "5_5") (pintype "passive"))
    )
    (net (code "110") (name "Net-(U10C-OUT)") (class "Default")
      (node (ref "PORTC") (pin "8") (pinfunction "8_8") (pintype "passive"))
      (node (ref "U10") (pin "8") (pinfunction "OUT_8") (pintype "output"))
      (node (ref "U5") (pin "5") (pinfunction "O_5") (pintype "output"))
      (node (ref "X3") (pin "6") (pinfunction "6_6") (pintype "passive"))
    )
    (net (code "111") (name "Net-(U10D-OUT)") (class "Default")
      (node (ref "PORTC") (pin "10") (pinfunction "10_10") (pintype "passive"))
      (node (ref "U10") (pin "14") (pinfunction "OUT_14") (pintype "output"))
      (node (ref "U6") (pin "7") (pinfunction "O_7") (pintype "output"))
      (node (ref "X3") (pin "8") (pinfunction "8_8") (pintype "passive"))
    )
    (net (code "112") (name "Net-(U11A-QA)") (class "Default")
      (node (ref "R3") (pin "1") (pinfunction "1_1") (pintype "passive"))
      (node (ref "U11") (pin "15") (pinfunction "QA_15") (pintype "tri_state"))
      (node (ref "U12") (pin "1") (pinfunction "I1_1") (pintype "input"))
    )
    (net (code "113") (name "Net-(U11A-QB)") (class "Default")
      (node (ref "R4") (pin "1") (pinfunction "1_1") (pintype "passive"))
      (node (ref "U11") (pin "1") (pinfunction "QB_1") (pintype "tri_state"))
      (node (ref "U12") (pin "2") (pinfunction "I2_2") (pintype "input"))
    )
    (net (code "114") (name "Net-(U11A-QC)") (class "Default")
      (node (ref "R5") (pin "1") (pinfunction "1_1") (pintype "passive"))
      (node (ref "U11") (pin "2") (pinfunction "QC_2") (pintype "tri_state"))
      (node (ref "U12") (pin "3") (pinfunction "I3_3") (pintype "input"))
    )
    (net (code "115") (name "Net-(U11A-QD)") (class "Default")
      (node (ref "R6") (pin "1") (pinfunction "1_1") (pintype "passive"))
      (node (ref "U11") (pin "3") (pinfunction "QD_3") (pintype "tri_state"))
      (node (ref "U12") (pin "4") (pinfunction "I4_4") (pintype "input"))
    )
    (net (code "116") (name "Net-(U11A-QE)") (class "Default")
      (node (ref "R7") (pin "1") (pinfunction "1_1") (pintype "passive"))
      (node (ref "U11") (pin "4") (pinfunction "QE_4") (pintype "tri_state"))
      (node (ref "U12") (pin "5") (pinfunction "I5_5") (pintype "input"))
    )
    (net (code "117") (name "Net-(U11A-QF)") (class "Default")
      (node (ref "R8") (pin "1") (pinfunction "1_1") (pintype "passive"))
      (node (ref "U11") (pin "5") (pinfunction "QF_5") (pintype "tri_state"))
      (node (ref "U12") (pin "6") (pinfunction "I6_6") (pintype "input"))
    )
    (net (code "118") (name "Net-(U11A-QG)") (class "Default")
      (node (ref "R9") (pin "1") (pinfunction "1_1") (pintype "passive"))
      (node (ref "U11") (pin "6") (pinfunction "QG_6") (pintype "tri_state"))
      (node (ref "U12") (pin "7") (pinfunction "I7_7") (pintype "input"))
    )
    (net (code "119") (name "Net-(U11A-QH)") (class "Default")
      (node (ref "R10") (pin "1") (pinfunction "1_1") (pintype "passive"))
      (node (ref "U11") (pin "7") (pinfunction "QH_7") (pintype "tri_state"))
      (node (ref "U12") (pin "8") (pinfunction "I8_8") (pintype "input"))
    )
    (net (code "120") (name "Net-(U13A-QA)") (class "Default")
      (node (ref "R11") (pin "1") (pinfunction "1_1") (pintype "passive"))
      (node (ref "U13") (pin "15") (pinfunction "QA_15") (pintype "tri_state"))
      (node (ref "U14") (pin "1") (pinfunction "I1_1") (pintype "input"))
    )
    (net (code "121") (name "Net-(U13A-QB)") (class "Default")
      (node (ref "R12") (pin "1") (pinfunction "1_1") (pintype "passive"))
      (node (ref "U13") (pin "1") (pinfunction "QB_1") (pintype "tri_state"))
      (node (ref "U14") (pin "2") (pinfunction "I2_2") (pintype "input"))
    )
    (net (code "122") (name "Net-(U13A-QC)") (class "Default")
      (node (ref "R13") (pin "1") (pinfunction "1_1") (pintype "passive"))
      (node (ref "U13") (pin "2") (pinfunction "QC_2") (pintype "tri_state"))
      (node (ref "U14") (pin "3") (pinfunction "I3_3") (pintype "input"))
    )
    (net (code "123") (name "Net-(U13A-QD)") (class "Default")
      (node (ref "R14") (pin "1") (pinfunction "1_1") (pintype "passive"))
      (node (ref "U13") (pin "3") (pinfunction "QD_3") (pintype "tri_state"))
      (node (ref "U14") (pin "4") (pinfunction "I4_4") (pintype "input"))
    )
    (net (code "124") (name "Net-(U13A-QE)") (class "Default")
      (node (ref "R15") (pin "1") (pinfunction "1_1") (pintype "passive"))
      (node (ref "U13") (pin "4") (pinfunction "QE_4") (pintype "tri_state"))
      (node (ref "U14") (pin "5") (pinfunction "I5_5") (pintype "input"))
    )
    (net (code "125") (name "Net-(U13A-QF)") (class "Default")
      (node (ref "R16") (pin "1") (pinfunction "1_1") (pintype "passive"))
      (node (ref "U13") (pin "5") (pinfunction "QF_5") (pintype "tri_state"))
      (node (ref "U14") (pin "6") (pinfunction "I6_6") (pintype "input"))
    )
    (net (code "126") (name "Net-(U13A-QG)") (class "Default")
      (node (ref "R17") (pin "1") (pinfunction "1_1") (pintype "passive"))
      (node (ref "U13") (pin "6") (pinfunction "QG_6") (pintype "tri_state"))
      (node (ref "U14") (pin "7") (pinfunction "I7_7") (pintype "input"))
    )
    (net (code "127") (name "Net-(U13A-QH)") (class "Default")
      (node (ref "R18") (pin "1") (pinfunction "1_1") (pintype "passive"))
      (node (ref "U13") (pin "7") (pinfunction "QH_7") (pintype "tri_state"))
      (node (ref "U14") (pin "8") (pinfunction "I8_8") (pintype "input"))
    )
    (net (code "128") (name "OLAT") (class "Default")
      (node (ref "R21") (pin "1") (pinfunction "1_1") (pintype "passive"))
      (node (ref "U$1") (pin "PA8") (pinfunction "PA8_PA8") (pintype "bidirectional"))
      (node (ref "U11") (pin "12") (pinfunction "RCK_12") (pintype "input"))
      (node (ref "U13") (pin "12") (pinfunction "RCK_12") (pintype "input"))
    )
    (net (code "129") (name "SCK") (class "Default")
      (node (ref "JP2") (pin "3") (pinfunction "3_3") (pintype "passive"))
      (node (ref "R19") (pin "1") (pinfunction "1_1") (pintype "passive"))
      (node (ref "U$1") (pin "PB3") (pinfunction "PB3_PB3") (pintype "bidirectional"))
      (node (ref "U11") (pin "11") (pinfunction "SCK_11") (pintype "input"))
      (node (ref "U13") (pin "11") (pinfunction "SCK_11") (pintype "input"))
    )
    (net (code "130") (name "SCK2") (class "Default")
      (node (ref "U$1") (pin "PB10") (pinfunction "PB10_PB10") (pintype "bidirectional"))
      (node (ref "U1") (pin "7") (pinfunction "CLK_7") (pintype "input"))
      (node (ref "U2") (pin "7") (pinfunction "CLK_7") (pintype "input"))
    )
    (net (code "131") (name "SLNK1") (class "Default")
      (node (ref "SJ17") (pin "P$1") (pinfunction "1_P$1") (pintype "passive"))
      (node (ref "U11") (pin "9") (pinfunction "QH*_9") (pintype "tri_state"))
      (node (ref "U13") (pin "14") (pinfunction "SER_14") (pintype "input"))
    )
    (net (code "132") (name "SLNK2") (class "Default")
      (node (ref "SJ16") (pin "P$1") (pinfunction "1_P$1") (pintype "passive"))
      (node (ref "U13") (pin "9") (pinfunction "QH*_9") (pintype "tri_state"))
    )
    (net (code "133") (name "SLNK3") (class "Default")
      (node (ref "SJ19") (pin "P$1") (pinfunction "1_P$1") (pintype "passive"))
      (node (ref "U1") (pin "13") (pinfunction "QH_13") (pintype "output"))
      (node (ref "U2") (pin "1") (pinfunction "SER_1") (pintype "input"))
    )
    (net (code "134") (name "SRV1") (class "Default")
      (node (ref "JP5") (pin "2") (pinfunction "2_2") (pintype "passive"))
      (node (ref "R24") (pin "2") (pinfunction "2_2") (pintype "passive"))
      (node (ref "U$1") (pin "PC9") (pinfunction "PC9_PC9") (pintype "bidirectional"))
    )
    (net (code "135") (name "SRV2") (class "Default")
      (node (ref "JP5") (pin "1") (pinfunction "1_1") (pintype "passive"))
      (node (ref "R25") (pin "2") (pinfunction "2_2") (pintype "passive"))
      (node (ref "U$1") (pin "PC7") (pinfunction "PC7_PC7") (pintype "bidirectional"))
    )
    (net (code "136") (name "SRV3") (class "Default")
      (node (ref "JP6") (pin "2") (pinfunction "2_2") (pintype "passive"))
      (node (ref "R26") (pin "2") (pinfunction "2_2") (pintype "passive"))
      (node (ref "U$1") (pin "PC8") (pinfunction "PC8_PC8") (pintype "bidirectional"))
    )
    (net (code "137") (name "SRV4") (class "Default")
      (node (ref "JP6") (pin "1") (pinfunction "1_1") (pintype "passive"))
      (node (ref "R27") (pin "2") (pinfunction "2_2") (pintype "passive"))
      (node (ref "U$1") (pin "PC6") (pinfunction "PC6_PC6") (pintype "bidirectional"))
    )
    (net (code "138") (name "SRV5") (class "Default")
      (node (ref "JP7") (pin "2") (pinfunction "2_2") (pintype "passive"))
      (node (ref "R64") (pin "2") (pinfunction "2_2") (pintype "passive"))
      (node (ref "U$1") (pin "PF1-PH1") (pinfunction "PF1-PH1_PF1-PH1") (pintype "bidirectional"))
    )
    (net (code "139") (name "SRV6") (class "Default")
      (node (ref "JP7") (pin "1") (pinfunction "1_1") (pintype "passive"))
      (node (ref "R65") (pin "2") (pinfunction "2_2") (pintype "passive"))
      (node (ref "U$1") (pin "PA15") (pinfunction "PA15_PA15") (pintype "bidirectional"))
    )
    (net (code "140") (name "SRV7") (class "Default")
      (node (ref "JP8") (pin "2") (pinfunction "2_2") (pintype "passive"))
      (node (ref "R66") (pin "2") (pinfunction "2_2") (pintype "passive"))
      (node (ref "U$1") (pin "PC12") (pinfunction "PC12_PC12") (pintype "bidirectional"))
    )
    (net (code "141") (name "SRV8") (class "Default")
      (node (ref "JP8") (pin "1") (pinfunction "1_1") (pintype "passive"))
      (node (ref "R67") (pin "2") (pinfunction "2_2") (pintype "passive"))
      (node (ref "U$1") (pin "PD2") (pinfunction "PD2_PD2") (pintype "bidirectional"))
    )
    (net (code "142") (name "TDRV1") (class "Default")
      (node (ref "U$1") (pin "PB12") (pinfunction "PB12_PB12") (pintype "bidirectional"))
      (node (ref "U10") (pin "12") (pinfunction "+IN_12") (pintype "input"))
      (node (ref "U6") (pin "2") (pinfunction "I_2") (pintype "input"))
    )
    (net (code "143") (name "TDRV2") (class "Default")
      (node (ref "U$1") (pin "PB2") (pinfunction "PB2_PB2") (pintype "bidirectional"))
      (node (ref "U10") (pin "3") (pinfunction "+IN_3") (pintype "input"))
      (node (ref "U6") (pin "4") (pinfunction "I_4") (pintype "input"))
    )
    (net (code "144") (name "TDRV3") (class "Default")
      (node (ref "U$1") (pin "PB15") (pinfunction "PB15_PB15") (pintype "bidirectional"))
      (node (ref "U10") (pin "10") (pinfunction "+IN_10") (pintype "input"))
      (node (ref "U5") (pin "4") (pinfunction "I_4") (pintype "input"))
    )
    (net (code "145") (name "TDRV4") (class "Default")
      (node (ref "U$1") (pin "PB1") (pinfunction "PB1_PB1") (pintype "bidirectional"))
      (node (ref "U10") (pin "5") (pinfunction "+IN_5") (pintype "input"))
      (node (ref "U5") (pin "2") (pinfunction "I_2") (pintype "input"))
    )
    (net (code "146") (name "TDRV5") (class "Default")
      (node (ref "U$1") (pin "PA0") (pinfunction "PA0_PA0") (pintype "bidirectional"))
      (node (ref "U4") (pin "2") (pinfunction "I_2") (pintype "input"))
      (node (ref "U9") (pin "12") (pinfunction "+IN_12") (pintype "input"))
    )
    (net (code "147") (name "TDRV6") (class "Default")
      (node (ref "U$1") (pin "PA4") (pinfunction "PA4_PA4") (pintype "bidirectional"))
      (node (ref "U4") (pin "4") (pinfunction "I_4") (pintype "input"))
      (node (ref "U9") (pin "3") (pinfunction "+IN_3") (pintype "input"))
    )
    (net (code "148") (name "TDRV7") (class "Default")
      (node (ref "U$1") (pin "PC3") (pinfunction "PC3_PC3") (pintype "bidirectional"))
      (node (ref "U3") (pin "4") (pinfunction "I_4") (pintype "input"))
      (node (ref "U9") (pin "10") (pinfunction "+IN_10") (pintype "input"))
    )
    (net (code "149") (name "TDRV8") (class "Default")
      (node (ref "U$1") (pin "PC0") (pinfunction "PC0_PC0") (pintype "bidirectional"))
      (node (ref "U3") (pin "2") (pinfunction "I_2") (pintype "input"))
      (node (ref "U9") (pin "5") (pinfunction "+IN_5") (pintype "input"))
    )
    (net (code "150") (name "V+") (class "Default")
      (node (ref "C1") (pin "1") (pinfunction "1_1") (pintype "passive"))
      (node (ref "C2") (pin "+") (pinfunction "+_+") (pintype "passive"))
      (node (ref "L1") (pin "1") (pinfunction "1_1") (pintype "passive"))
      (node (ref "U$1") (pin "E5V") (pinfunction "E5V_E5V") (pintype "power_in"))
      (node (ref "U8") (pin "3") (pinfunction "FB_3") (pintype "bidirectional"))
      (node (ref "U8B") (pin "1") (pinfunction "FB_1") (pintype "input"))
    )
    (net (code "151") (name "unconnected-(H1-MOUNT-PadB3,3)") (class "Default")
      (node (ref "H1") (pin "B3,3") (pinfunction "MOUNT_B3,3") (pintype "passive"))
    )
    (net (code "152") (name "unconnected-(H2-MOUNT-PadB3,3)") (class "Default")
      (node (ref "H2") (pin "B3,3") (pinfunction "MOUNT_B3,3") (pintype "passive"))
    )
    (net (code "153") (name "unconnected-(H3-MOUNT-PadB3,3)") (class "Default")
      (node (ref "H3") (pin "B3,3") (pinfunction "MOUNT_B3,3") (pintype "passive"))
    )
    (net (code "154") (name "unconnected-(H4-MOUNT-PadB3,3)") (class "Default")
      (node (ref "H4") (pin "B3,3") (pinfunction "MOUNT_B3,3") (pintype "passive"))
    )
    (net (code "155") (name "unconnected-(U$1-PadBOOT0)") (class "Default")
      (node (ref "U$1") (pin "BOOT0") (pinfunction "BOOT0_BOOT0") (pintype "bidirectional"))
    )
    (net (code "156") (name "unconnected-(U$1-PadIOREF2)") (class "Default")
      (node (ref "U$1") (pin "IOREF2") (pinfunction "IOREF2_IOREF2") (pintype "input"))
    )
    (net (code "157") (name "unconnected-(U$1-PadNC1-PF7)") (class "Default")
      (node (ref "U$1") (pin "NC1-PF7") (pinfunction "NC1-PF7_NC1-PF7") (pintype "bidirectional"))
    )
    (net (code "158") (name "unconnected-(U$1-PadNC2-PF6)") (class "Default")
      (node (ref "U$1") (pin "NC2-PF6") (pinfunction "NC2-PF6_NC2-PF6") (pintype "bidirectional"))
    )
    (net (code "159") (name "unconnected-(U$1-PadNC3)") (class "Default")
      (node (ref "U$1") (pin "NC3") (pinfunction "NC3_NC3") (pintype "no_connect"))
    )
    (net (code "160") (name "unconnected-(U$1-PadNC4)") (class "Default")
      (node (ref "U$1") (pin "NC4") (pinfunction "NC4_NC4") (pintype "no_connect"))
    )
    (net (code "161") (name "unconnected-(U$1-PadNC5-PD8)") (class "Default")
      (node (ref "U$1") (pin "NC5-PD8") (pinfunction "NC5-PD8_NC5-PD8") (pintype "bidirectional"))
    )
    (net (code "162") (name "unconnected-(U$1-PadNC6-PB11)") (class "Default")
      (node (ref "U$1") (pin "NC6-PB11") (pinfunction "NC6-PB11_NC6-PB11") (pintype "no_connect"))
    )
    (net (code "163") (name "unconnected-(U$1-PadNC7-PF5)") (class "Default")
      (node (ref "U$1") (pin "NC7-PF5") (pinfunction "NC7-PF5_NC7-PF5") (pintype "bidirectional"))
    )
    (net (code "164") (name "unconnected-(U$1-PadNC8-PF4)") (class "Default")
      (node (ref "U$1") (pin "NC8-PF4") (pinfunction "NC8-PF4_NC8-PF4") (pintype "bidirectional"))
    )
    (net (code "165") (name "unconnected-(U$1-PadNRESET)") (class "Default")
      (node (ref "U$1") (pin "NRESET") (pinfunction "NRESET_NRESET") (pintype "input"))
    )
    (net (code "166") (name "unconnected-(U$1-PadPA1)") (class "Default")
      (node (ref "U$1") (pin "PA1") (pinfunction "PA1_PA1") (pintype "bidirectional"))
    )
    (net (code "167") (name "unconnected-(U$1-PadPA2)") (class "Default")
      (node (ref "U$1") (pin "PA2") (pinfunction "PA2_PA2") (pintype "bidirectional"))
    )
    (net (code "168") (name "unconnected-(U$1-PadPA3)") (class "Default")
      (node (ref "U$1") (pin "PA3") (pinfunction "PA3_PA3") (pintype "bidirectional"))
    )
    (net (code "169") (name "unconnected-(U$1-PadPA5)") (class "Default")
      (node (ref "U$1") (pin "PA5") (pinfunction "PA5_PA5") (pintype "bidirectional"))
    )
    (net (code "170") (name "unconnected-(U$1-PadPA7)") (class "Default")
      (node (ref "U$1") (pin "PA7") (pinfunction "PA7_PA7") (pintype "bidirectional"))
    )
    (net (code "171") (name "unconnected-(U$1-PadPA9)") (class "Default")
      (node (ref "U$1") (pin "PA9") (pinfunction "PA9_PA9") (pintype "bidirectional"))
    )
    (net (code "172") (name "unconnected-(U$1-PadPA10)") (class "Default")
      (node (ref "U$1") (pin "PA10") (pinfunction "PA10_PA10") (pintype "bidirectional"))
    )
    (net (code "173") (name "unconnected-(U$1-PadPA11)") (class "Default")
      (node (ref "U$1") (pin "PA11") (pinfunction "PA11_PA11") (pintype "bidirectional"))
    )
    (net (code "174") (name "unconnected-(U$1-PadPA12)") (class "Default")
      (node (ref "U$1") (pin "PA12") (pinfunction "PA12_PA12") (pintype "bidirectional"))
    )
    (net (code "175") (name "unconnected-(U$1-PadPA13)") (class "Default")
      (node (ref "U$1") (pin "PA13") (pinfunction "PA13_PA13") (pintype "bidirectional"))
    )
    (net (code "176") (name "unconnected-(U$1-PadPA14)") (class "Default")
      (node (ref "U$1") (pin "PA14") (pinfunction "PA14_PA14") (pintype "bidirectional"))
    )
    (net (code "177") (name "unconnected-(U$1-PadPB0)") (class "Default")
      (node (ref "U$1") (pin "PB0") (pinfunction "PB0_PB0") (pintype "bidirectional"))
    )
    (net (code "178") (name "unconnected-(U$1-PadPB13)") (class "Default")
      (node (ref "U$1") (pin "PB13") (pinfunction "PB13_PB13") (pintype "bidirectional"))
    )
    (net (code "179") (name "unconnected-(U$1-PadPC1)") (class "Default")
      (node (ref "U$1") (pin "PC1") (pinfunction "PC1_PC1") (pintype "bidirectional"))
    )
    (net (code "180") (name "unconnected-(U$1-PadPC4)") (class "Default")
      (node (ref "U$1") (pin "PC4") (pinfunction "PC4_PC4") (pintype "bidirectional"))
    )
    (net (code "181") (name "unconnected-(U$1-PadPC5)") (class "Default")
      (node (ref "U$1") (pin "PC5") (pinfunction "PC5_PC5") (pintype "bidirectional"))
    )
    (net (code "182") (name "unconnected-(U$1-PadPC13)") (class "Default")
      (node (ref "U$1") (pin "PC13") (pinfunction "PC13_PC13") (pintype "bidirectional"))
    )
    (net (code "183") (name "unconnected-(U$1-PadPC14)") (class "Default")
      (node (ref "U$1") (pin "PC14") (pinfunction "PC14_PC14") (pintype "bidirectional"))
    )
    (net (code "184") (name "unconnected-(U$1-PadPC15)") (class "Default")
      (node (ref "U$1") (pin "PC15") (pinfunction "PC15_PC15") (pintype "bidirectional"))
    )
    (net (code "185") (name "unconnected-(U$1-PadPF0-PH0)") (class "Default")
      (node (ref "U$1") (pin "PF0-PH0") (pinfunction "PF0-PH0_PF0-PH0") (pintype "bidirectional"))
    )
  )
)
